# CNC_IO_Buffer_Cape.net
KiCad netlist of a schematic drawn in EAGLE
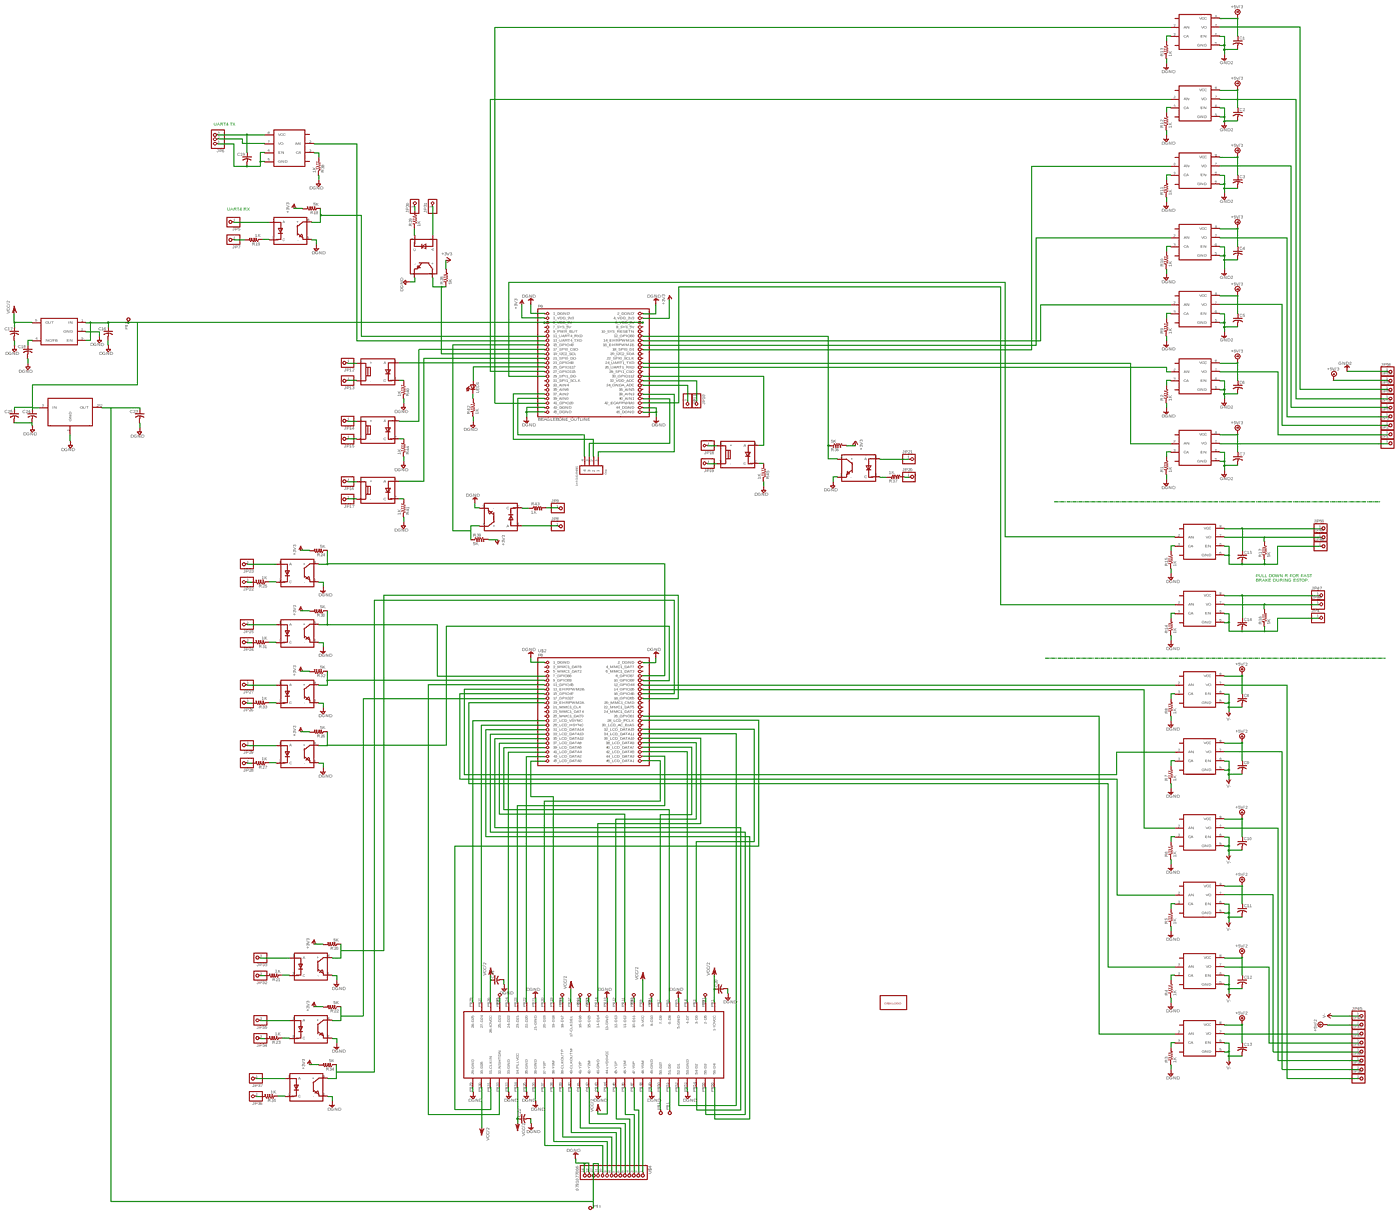
[diagram p0: schematic, sheet 1, overview]
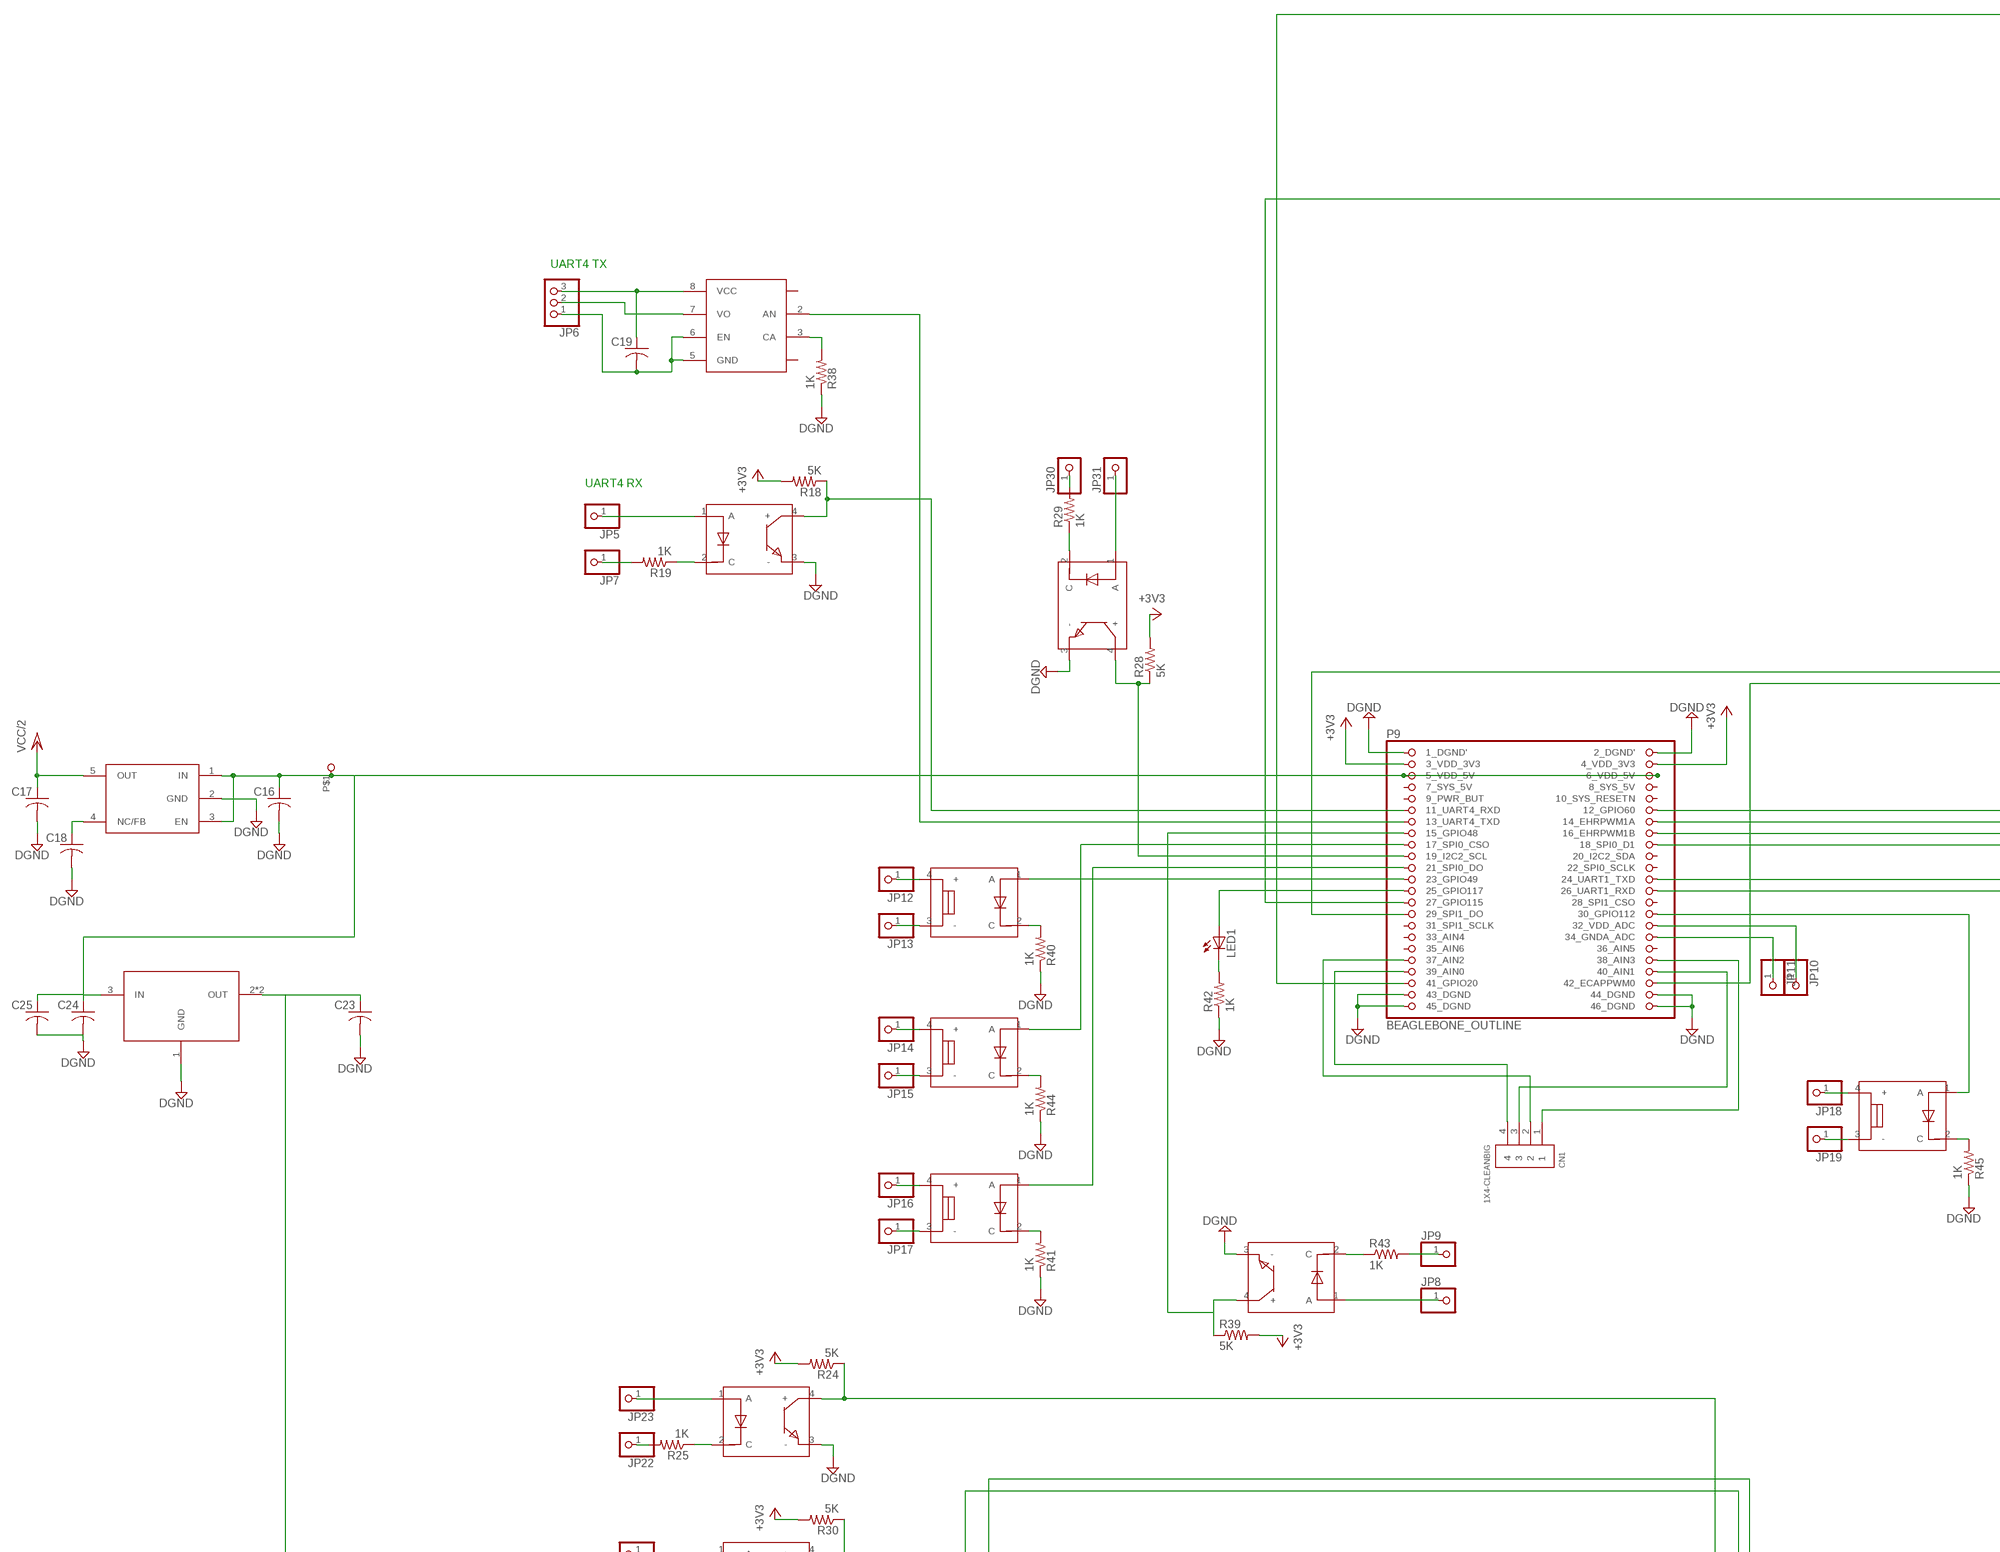
[diagram p1: schematic, sheet 1, part 1 of 4]
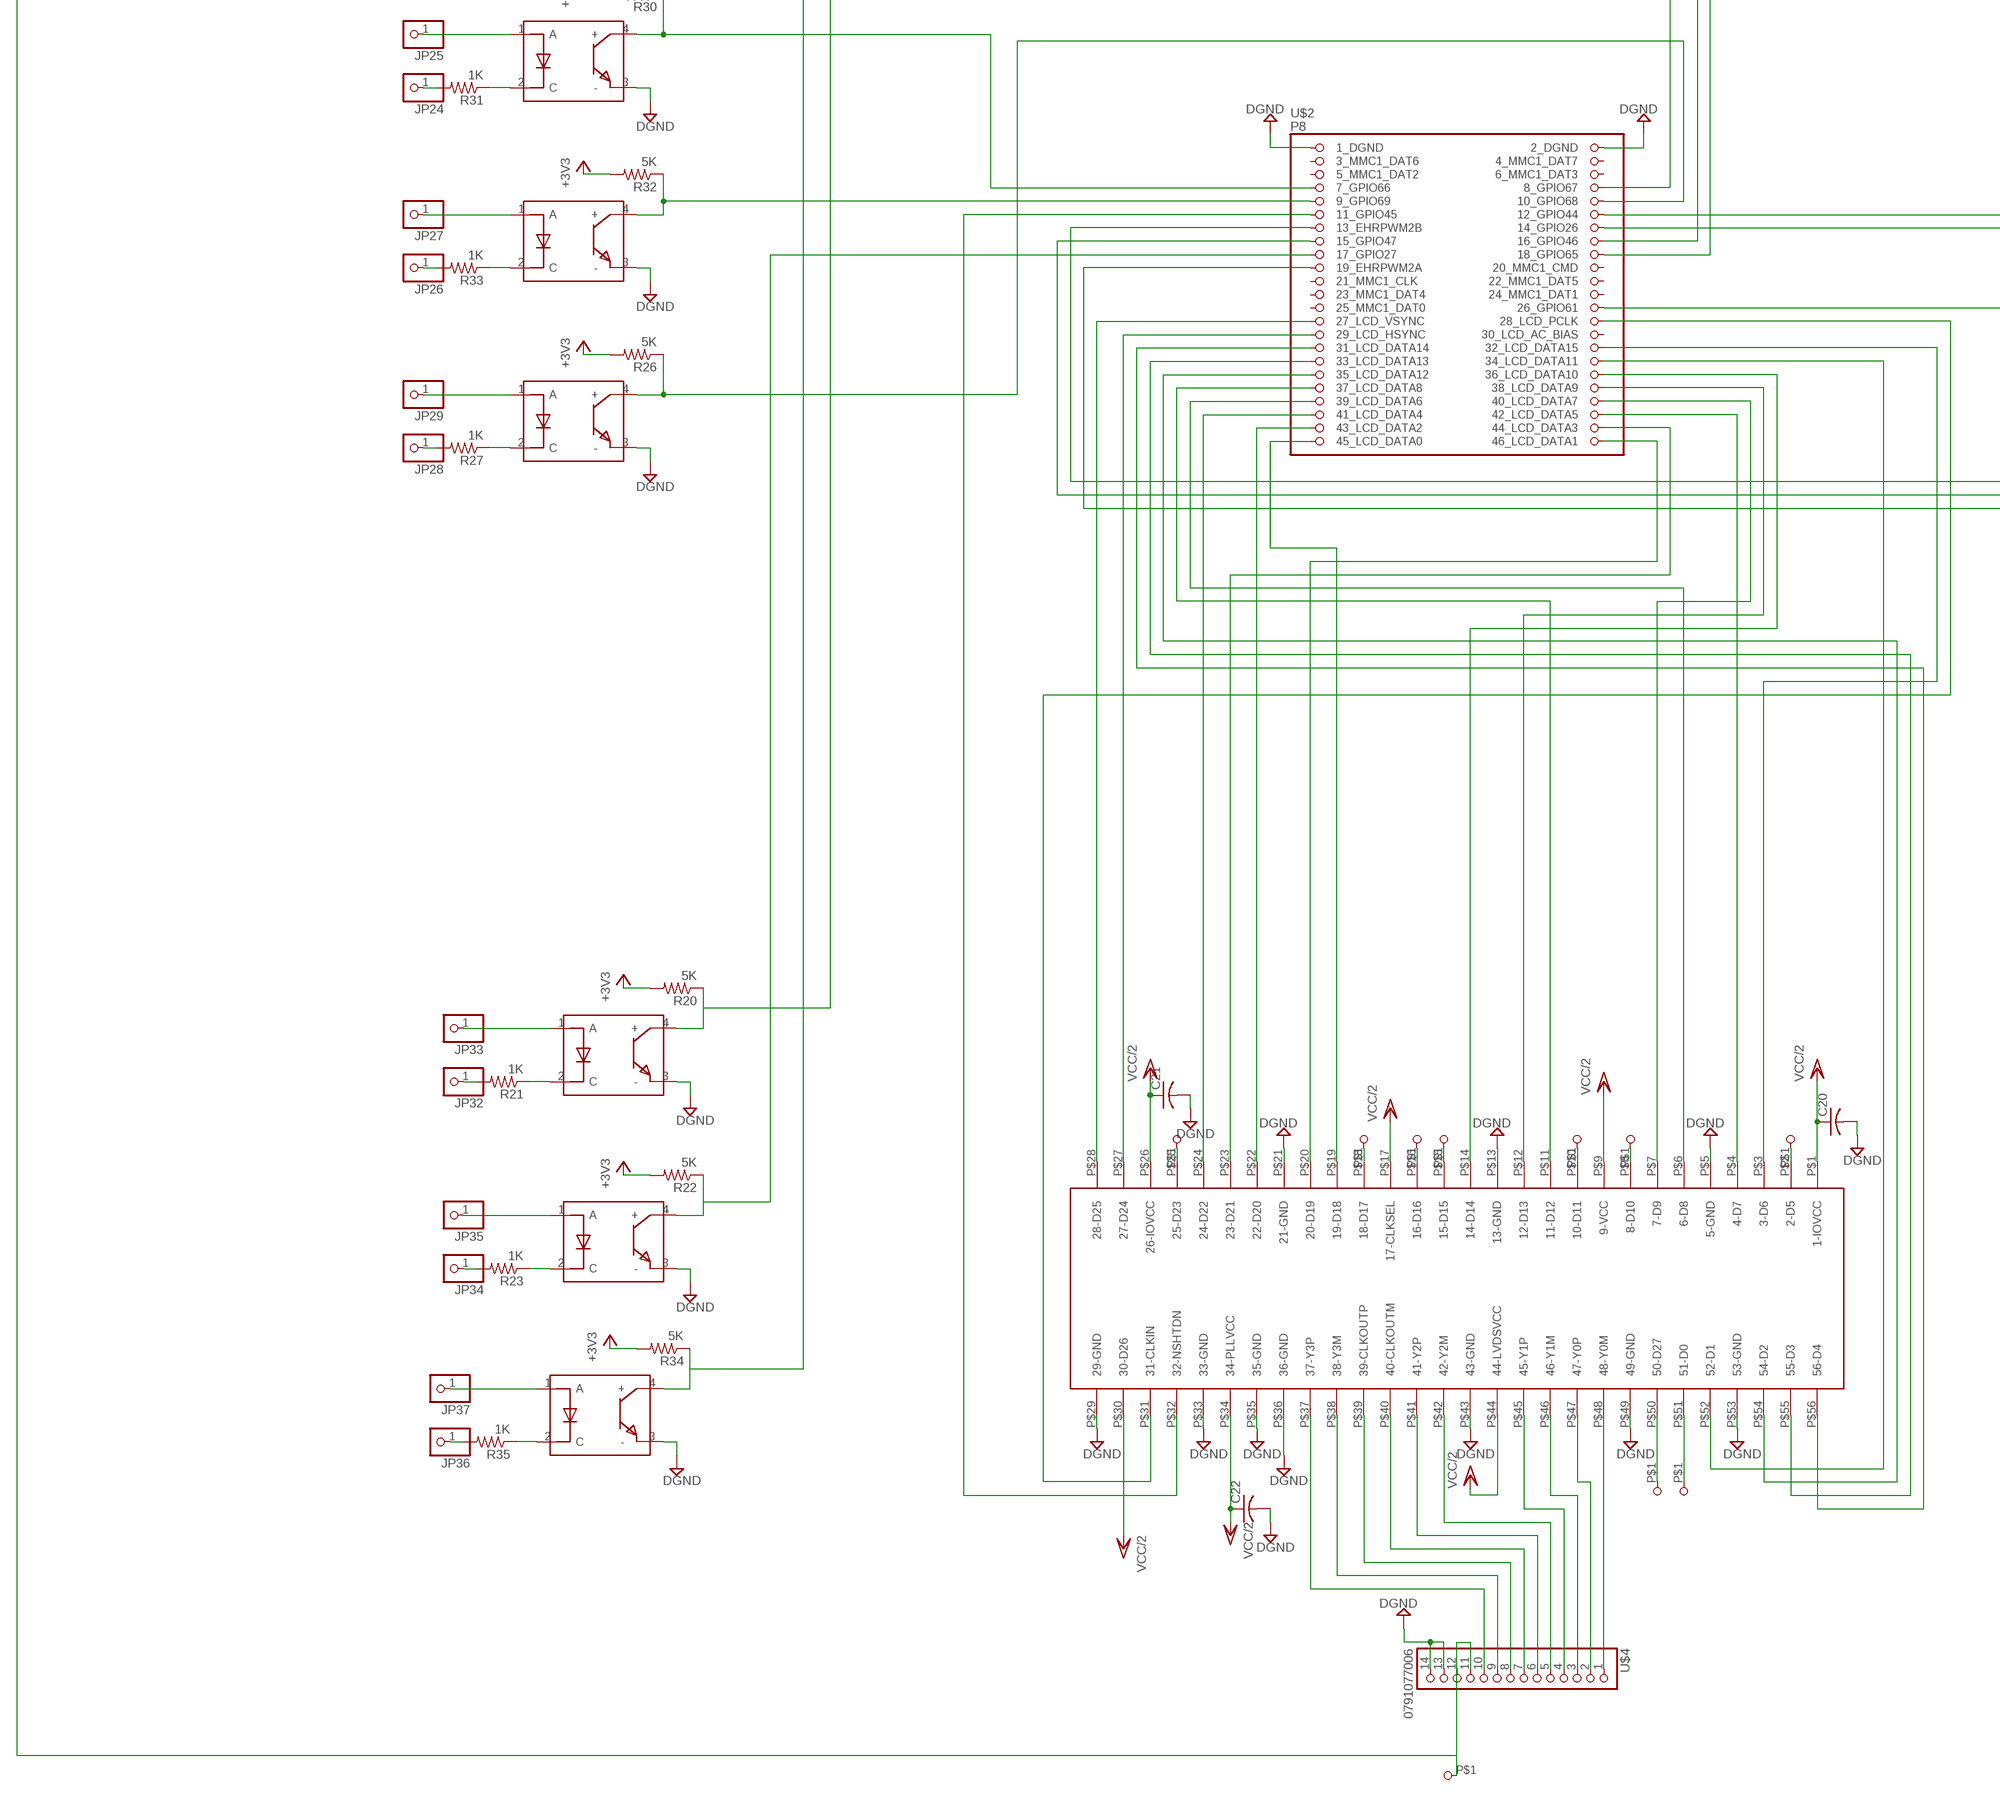
[diagram p2: schematic, sheet 1, part 2 of 4]
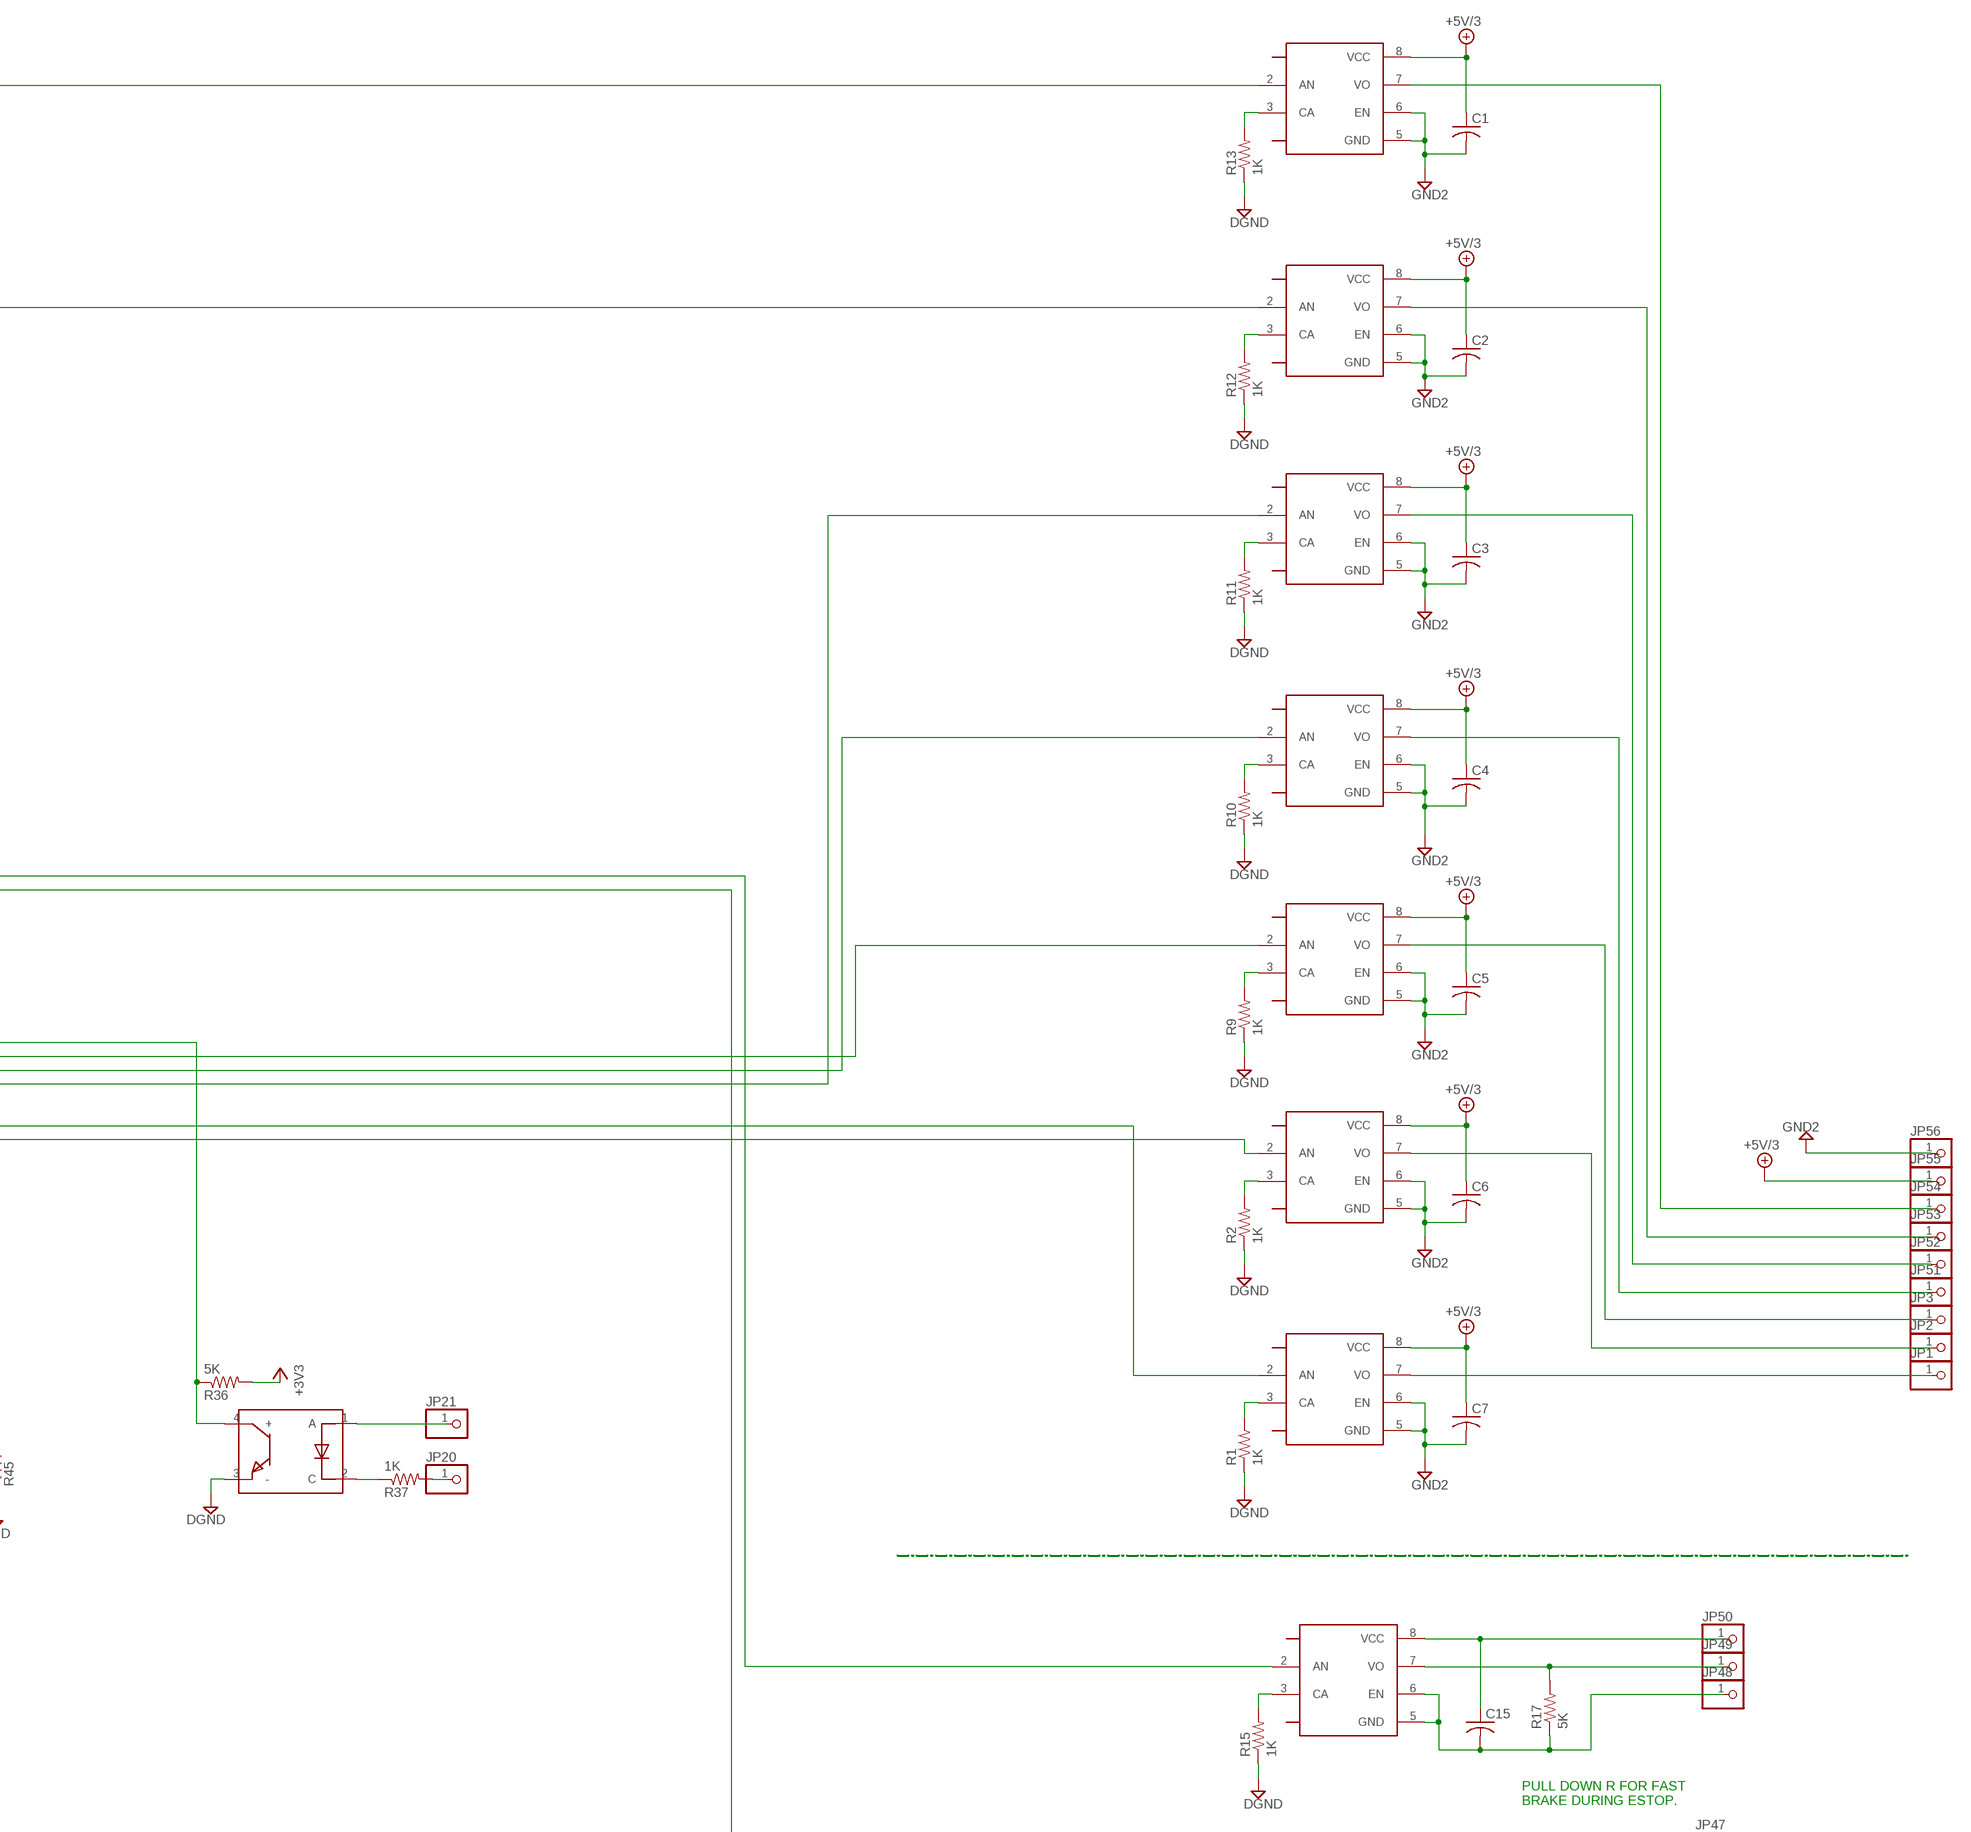
[diagram p3: schematic, sheet 1, part 3 of 4]
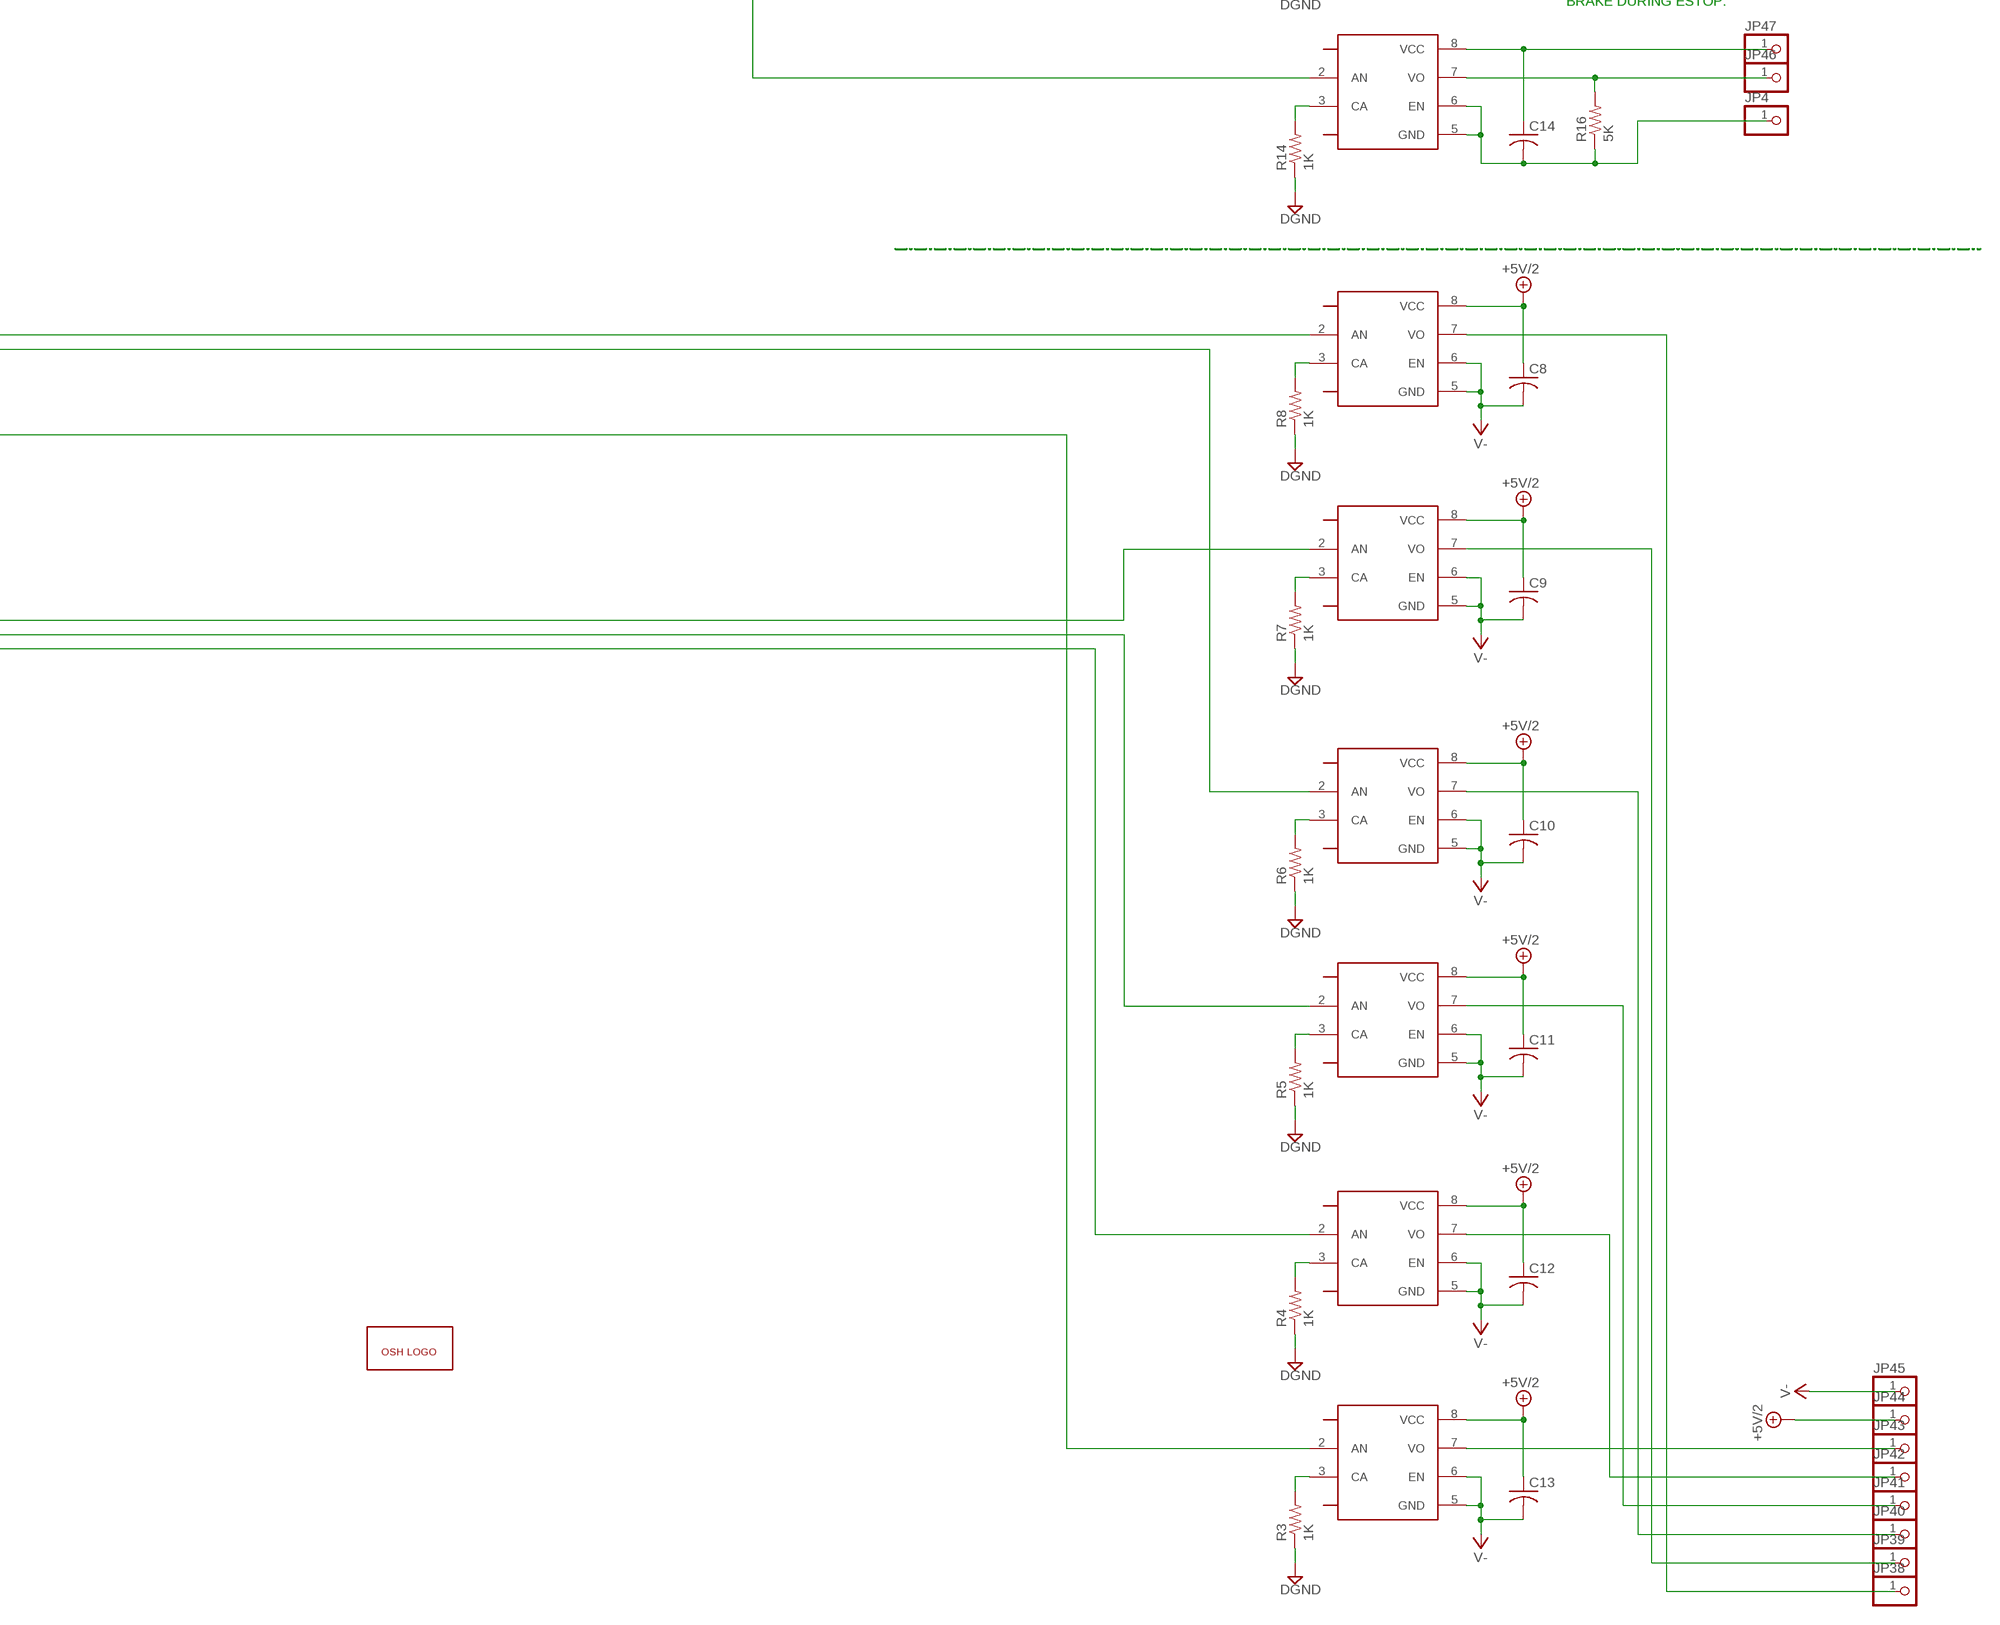
[diagram p4: schematic, sheet 1, part 4 of 4]

(export (version "E")
  (design (tool "Eeschema 10.0.6"))
  (components
    (comp (ref "0000")
      (value "TLP2200F")
      (footprint "eagle-import:DIL08-ROUND")
      (libsource (lib "eagle-import") (part "TLP2200F"))
    )
    (comp (ref "8.12")
      (value "TLP2200F")
      (footprint "eagle-import:DIL08-ROUND")
      (libsource (lib "eagle-import") (part "TLP2200F"))
    )
    (comp (ref "8.13")
      (value "TLP2200F")
      (footprint "eagle-import:DIL08-ROUND")
      (libsource (lib "eagle-import") (part "TLP2200F"))
    )
    (comp (ref "8.14")
      (value "TLP2200F")
      (footprint "eagle-import:DIL08-ROUND")
      (libsource (lib "eagle-import") (part "TLP2200F"))
    )
    (comp (ref "8.15")
      (value "TLP2200F")
      (footprint "eagle-import:DIL08-ROUND")
      (libsource (lib "eagle-import") (part "TLP2200F"))
    )
    (comp (ref "8.19")
      (value "TLP2200F")
      (footprint "eagle-import:DIL08-ROUND")
      (libsource (lib "eagle-import") (part "TLP2200F"))
    )
    (comp (ref "8.26")
      (value "TLP2200F")
      (footprint "eagle-import:DIL08-ROUND")
      (libsource (lib "eagle-import") (part "TLP2200F"))
    )
    (comp (ref "9.3")
      (value "TLP2200F")
      (footprint "eagle-import:DIL08-ROUND")
      (libsource (lib "eagle-import") (part "TLP2200F"))
    )
    (comp (ref "9.14")
      (value "TLP2200F")
      (footprint "eagle-import:DIL08-ROUND")
      (libsource (lib "eagle-import") (part "TLP2200F"))
    )
    (comp (ref "9.16")
      (value "TLP2200F")
      (footprint "eagle-import:DIL08-ROUND")
      (libsource (lib "eagle-import") (part "TLP2200F"))
    )
    (comp (ref "9.18")
      (value "TLP2200F")
      (footprint "eagle-import:DIL08-ROUND")
      (libsource (lib "eagle-import") (part "TLP2200F"))
    )
    (comp (ref "9.24")
      (value "TLP2200F")
      (footprint "eagle-import:DIL08-ROUND")
      (libsource (lib "eagle-import") (part "TLP2200F"))
    )
    (comp (ref "9.26")
      (value "TLP2200F")
      (footprint "eagle-import:DIL08-ROUND")
      (libsource (lib "eagle-import") (part "TLP2200F"))
    )
    (comp (ref "9.27")
      (value "TLP2200F")
      (footprint "eagle-import:DIL08-ROUND")
      (libsource (lib "eagle-import") (part "TLP2200F"))
    )
    (comp (ref "9.41")
      (value "TLP2200F")
      (footprint "eagle-import:DIL08-ROUND")
      (libsource (lib "eagle-import") (part "TLP2200F"))
    )
    (comp (ref "1111")
      (value "TLP2200F")
      (footprint "eagle-import:DIL08-ROUND")
      (libsource (lib "eagle-import") (part "TLP2200F"))
    )
    (comp (ref "C1")
      (value "C-USC0805K")
      (footprint "eagle-import:C0805K")
      (libsource (lib "eagle-import") (part "rcl_C-USC0805K"))
    )
    (comp (ref "C2")
      (value "C-USC0805K")
      (footprint "eagle-import:C0805K")
      (libsource (lib "eagle-import") (part "rcl_C-USC0805K"))
    )
    (comp (ref "C3")
      (value "C-USC0805K")
      (footprint "eagle-import:C0805K")
      (libsource (lib "eagle-import") (part "rcl_C-USC0805K"))
    )
    (comp (ref "C4")
      (value "C-USC0805K")
      (footprint "eagle-import:C0805K")
      (libsource (lib "eagle-import") (part "rcl_C-USC0805K"))
    )
    (comp (ref "C5")
      (value "C-USC0805K")
      (footprint "eagle-import:C0805K")
      (libsource (lib "eagle-import") (part "rcl_C-USC0805K"))
    )
    (comp (ref "C6")
      (value "C-USC0805K")
      (footprint "eagle-import:C0805K")
      (libsource (lib "eagle-import") (part "rcl_C-USC0805K"))
    )
    (comp (ref "C7")
      (value "C-USC0805K")
      (footprint "eagle-import:C0805K")
      (libsource (lib "eagle-import") (part "rcl_C-USC0805K"))
    )
    (comp (ref "C8")
      (value "C-USC0805K")
      (footprint "eagle-import:C0805K")
      (libsource (lib "eagle-import") (part "rcl_C-USC0805K"))
    )
    (comp (ref "C9")
      (value "C-USC0805K")
      (footprint "eagle-import:C0805K")
      (libsource (lib "eagle-import") (part "rcl_C-USC0805K"))
    )
    (comp (ref "C10")
      (value "C-USC0805K")
      (footprint "eagle-import:C0805K")
      (libsource (lib "eagle-import") (part "rcl_C-USC0805K"))
    )
    (comp (ref "C11")
      (value "C-USC0805K")
      (footprint "eagle-import:C0805K")
      (libsource (lib "eagle-import") (part "rcl_C-USC0805K"))
    )
    (comp (ref "C12")
      (value "C-USC0805K")
      (footprint "eagle-import:C0805K")
      (libsource (lib "eagle-import") (part "rcl_C-USC0805K"))
    )
    (comp (ref "C13")
      (value "C-USC0805K")
      (footprint "eagle-import:C0805K")
      (libsource (lib "eagle-import") (part "rcl_C-USC0805K"))
    )
    (comp (ref "C14")
      (value "C-USC0805K")
      (footprint "eagle-import:C0805K")
      (libsource (lib "eagle-import") (part "rcl_C-USC0805K"))
    )
    (comp (ref "C15")
      (value "C-USC0805K")
      (footprint "eagle-import:C0805K")
      (libsource (lib "eagle-import") (part "rcl_C-USC0805K"))
    )
    (comp (ref "C16")
      (value "C-USC0805K")
      (footprint "eagle-import:C0805K")
      (libsource (lib "eagle-import") (part "C-USC0805K"))
    )
    (comp (ref "C17")
      (value "C-USC0805K")
      (footprint "eagle-import:C0805K")
      (libsource (lib "eagle-import") (part "C-USC0805K"))
    )
    (comp (ref "C18")
      (value "C-USC0402")
      (footprint "eagle-import:C0402")
      (libsource (lib "eagle-import") (part "C-USC0402"))
    )
    (comp (ref "C19")
      (value "C-USC0805K")
      (footprint "eagle-import:C0805K")
      (libsource (lib "eagle-import") (part "rcl_C-USC0805K"))
    )
    (comp (ref "C20")
      (value "C-USC0402")
      (footprint "eagle-import:C0402")
      (libsource (lib "eagle-import") (part "C-USC0402"))
    )
    (comp (ref "C21")
      (value "C-USC0402")
      (footprint "eagle-import:C0402")
      (libsource (lib "eagle-import") (part "C-USC0402"))
    )
    (comp (ref "C22")
      (value "C-USC0402")
      (footprint "eagle-import:C0402")
      (libsource (lib "eagle-import") (part "C-USC0402"))
    )
    (comp (ref "C23")
      (value "C-USC0805K")
      (footprint "eagle-import:C0805K")
      (libsource (lib "eagle-import") (part "C-USC0805K"))
    )
    (comp (ref "C24")
      (value "C-USC0805K")
      (footprint "eagle-import:C0805K")
      (libsource (lib "eagle-import") (part "C-USC0805K"))
    )
    (comp (ref "C25")
      (value "C-USC0402")
      (footprint "eagle-import:C0402")
      (libsource (lib "eagle-import") (part "C-USC0402"))
    )
    (comp (ref "CN1")
      (value "1X4-CLEANBIG")
      (footprint "eagle-import:1X04-CLEANBIG")
      (libsource (lib "eagle-import") (part "1X4-CLEANBIG"))
    )
    (comp (ref "JP1")
      (value "PINHD-1X1CB")
      (footprint "eagle-import:1X01-CLEANBIG")
      (libsource (lib "eagle-import") (part "PINHD-1X1CB"))
    )
    (comp (ref "JP2")
      (value "PINHD-1X1CB")
      (footprint "eagle-import:1X01-CLEANBIG")
      (libsource (lib "eagle-import") (part "PINHD-1X1CB"))
    )
    (comp (ref "JP3")
      (value "PINHD-1X1CB")
      (footprint "eagle-import:1X01-CLEANBIG")
      (libsource (lib "eagle-import") (part "PINHD-1X1CB"))
    )
    (comp (ref "JP4")
      (value "PINHD-1X1CB")
      (footprint "eagle-import:1X01-CLEANBIG")
      (libsource (lib "eagle-import") (part "PINHD-1X1CB"))
    )
    (comp (ref "JP5")
      (value "PINHD-1X1CB")
      (footprint "eagle-import:1X01-CLEANBIG")
      (libsource (lib "eagle-import") (part "PINHD-1X1CB"))
    )
    (comp (ref "JP6")
      (value "PINHD-1X3CB")
      (footprint "eagle-import:1X03-CLEANBIG")
      (libsource (lib "eagle-import") (part "PINHD-1X3CB"))
    )
    (comp (ref "JP7")
      (value "PINHD-1X1CB")
      (footprint "eagle-import:1X01-CLEANBIG")
      (libsource (lib "eagle-import") (part "PINHD-1X1CB"))
    )
    (comp (ref "JP8")
      (value "PINHD-1X1CB")
      (footprint "eagle-import:1X01-CLEANBIG")
      (libsource (lib "eagle-import") (part "PINHD-1X1CB"))
    )
    (comp (ref "JP9")
      (value "PINHD-1X1CB")
      (footprint "eagle-import:1X01-CLEANBIG")
      (libsource (lib "eagle-import") (part "PINHD-1X1CB"))
    )
    (comp (ref "JP10")
      (value "PINHD-1X1CB")
      (footprint "eagle-import:1X01-CLEANBIG")
      (libsource (lib "eagle-import") (part "PINHD-1X1CB"))
    )
    (comp (ref "JP11")
      (value "PINHD-1X1CB")
      (footprint "eagle-import:1X01-CLEANBIG")
      (libsource (lib "eagle-import") (part "PINHD-1X1CB"))
    )
    (comp (ref "JP12")
      (value "PINHD-1X1CB")
      (footprint "eagle-import:1X01-CLEANBIG")
      (libsource (lib "eagle-import") (part "PINHD-1X1CB"))
    )
    (comp (ref "JP13")
      (value "PINHD-1X1CB")
      (footprint "eagle-import:1X01-CLEANBIG")
      (libsource (lib "eagle-import") (part "PINHD-1X1CB"))
    )
    (comp (ref "JP14")
      (value "PINHD-1X1CB")
      (footprint "eagle-import:1X01-CLEANBIG")
      (libsource (lib "eagle-import") (part "PINHD-1X1CB"))
    )
    (comp (ref "JP15")
      (value "PINHD-1X1CB")
      (footprint "eagle-import:1X01-CLEANBIG")
      (libsource (lib "eagle-import") (part "PINHD-1X1CB"))
    )
    (comp (ref "JP16")
      (value "PINHD-1X1CB")
      (footprint "eagle-import:1X01-CLEANBIG")
      (libsource (lib "eagle-import") (part "PINHD-1X1CB"))
    )
    (comp (ref "JP17")
      (value "PINHD-1X1CB")
      (footprint "eagle-import:1X01-CLEANBIG")
      (libsource (lib "eagle-import") (part "PINHD-1X1CB"))
    )
    (comp (ref "JP18")
      (value "PINHD-1X1CB")
      (footprint "eagle-import:1X01-CLEANBIG")
      (libsource (lib "eagle-import") (part "PINHD-1X1CB"))
    )
    (comp (ref "JP19")
      (value "PINHD-1X1CB")
      (footprint "eagle-import:1X01-CLEANBIG")
      (libsource (lib "eagle-import") (part "PINHD-1X1CB"))
    )
    (comp (ref "JP20")
      (value "PINHD-1X1CB")
      (footprint "eagle-import:1X01-CLEANBIG")
      (libsource (lib "eagle-import") (part "PINHD-1X1CB"))
    )
    (comp (ref "JP21")
      (value "PINHD-1X1CB")
      (footprint "eagle-import:1X01-CLEANBIG")
      (libsource (lib "eagle-import") (part "PINHD-1X1CB"))
    )
    (comp (ref "JP22")
      (value "PINHD-1X1CB")
      (footprint "eagle-import:1X01-CLEANBIG")
      (libsource (lib "eagle-import") (part "PINHD-1X1CB"))
    )
    (comp (ref "JP23")
      (value "PINHD-1X1CB")
      (footprint "eagle-import:1X01-CLEANBIG")
      (libsource (lib "eagle-import") (part "PINHD-1X1CB"))
    )
    (comp (ref "JP24")
      (value "PINHD-1X1CB")
      (footprint "eagle-import:1X01-CLEANBIG")
      (libsource (lib "eagle-import") (part "PINHD-1X1CB"))
    )
    (comp (ref "JP25")
      (value "PINHD-1X1CB")
      (footprint "eagle-import:1X01-CLEANBIG")
      (libsource (lib "eagle-import") (part "PINHD-1X1CB"))
    )
    (comp (ref "JP26")
      (value "PINHD-1X1CB")
      (footprint "eagle-import:1X01-CLEANBIG")
      (libsource (lib "eagle-import") (part "PINHD-1X1CB"))
    )
    (comp (ref "JP27")
      (value "PINHD-1X1CB")
      (footprint "eagle-import:1X01-CLEANBIG")
      (libsource (lib "eagle-import") (part "PINHD-1X1CB"))
    )
    (comp (ref "JP28")
      (value "PINHD-1X1CB")
      (footprint "eagle-import:1X01-CLEANBIG")
      (libsource (lib "eagle-import") (part "PINHD-1X1CB"))
    )
    (comp (ref "JP29")
      (value "PINHD-1X1CB")
      (footprint "eagle-import:1X01-CLEANBIG")
      (libsource (lib "eagle-import") (part "PINHD-1X1CB"))
    )
    (comp (ref "JP30")
      (value "PINHD-1X1CB")
      (footprint "eagle-import:1X01-CLEANBIG")
      (libsource (lib "eagle-import") (part "PINHD-1X1CB"))
    )
    (comp (ref "JP31")
      (value "PINHD-1X1CB")
      (footprint "eagle-import:1X01-CLEANBIG")
      (libsource (lib "eagle-import") (part "PINHD-1X1CB"))
    )
    (comp (ref "JP32")
      (value "PINHD-1X1CB")
      (footprint "eagle-import:1X01-CLEANBIG")
      (libsource (lib "eagle-import") (part "PINHD-1X1CB"))
    )
    (comp (ref "JP33")
      (value "PINHD-1X1CB")
      (footprint "eagle-import:1X01-CLEANBIG")
      (libsource (lib "eagle-import") (part "PINHD-1X1CB"))
    )
    (comp (ref "JP34")
      (value "PINHD-1X1CB")
      (footprint "eagle-import:1X01-CLEANBIG")
      (libsource (lib "eagle-import") (part "PINHD-1X1CB"))
    )
    (comp (ref "JP35")
      (value "PINHD-1X1CB")
      (footprint "eagle-import:1X01-CLEANBIG")
      (libsource (lib "eagle-import") (part "PINHD-1X1CB"))
    )
    (comp (ref "JP36")
      (value "PINHD-1X1CB")
      (footprint "eagle-import:1X01-CLEANBIG")
      (libsource (lib "eagle-import") (part "PINHD-1X1CB"))
    )
    (comp (ref "JP37")
      (value "PINHD-1X1CB")
      (footprint "eagle-import:1X01-CLEANBIG")
      (libsource (lib "eagle-import") (part "PINHD-1X1CB"))
    )
    (comp (ref "JP38")
      (value "PINHD-1X1CB")
      (footprint "eagle-import:1X01-CLEANBIG")
      (libsource (lib "eagle-import") (part "PINHD-1X1CB"))
    )
    (comp (ref "JP39")
      (value "PINHD-1X1CB")
      (footprint "eagle-import:1X01-CLEANBIG")
      (libsource (lib "eagle-import") (part "PINHD-1X1CB"))
    )
    (comp (ref "JP40")
      (value "PINHD-1X1CB")
      (footprint "eagle-import:1X01-CLEANBIG")
      (libsource (lib "eagle-import") (part "PINHD-1X1CB"))
    )
    (comp (ref "JP41")
      (value "PINHD-1X1CB")
      (footprint "eagle-import:1X01-CLEANBIG")
      (libsource (lib "eagle-import") (part "PINHD-1X1CB"))
    )
    (comp (ref "JP42")
      (value "PINHD-1X1CB")
      (footprint "eagle-import:1X01-CLEANBIG")
      (libsource (lib "eagle-import") (part "PINHD-1X1CB"))
    )
    (comp (ref "JP43")
      (value "PINHD-1X1CB")
      (footprint "eagle-import:1X01-CLEANBIG")
      (libsource (lib "eagle-import") (part "PINHD-1X1CB"))
    )
    (comp (ref "JP44")
      (value "PINHD-1X1CB")
      (footprint "eagle-import:1X01-CLEANBIG")
      (libsource (lib "eagle-import") (part "PINHD-1X1CB"))
    )
    (comp (ref "JP45")
      (value "PINHD-1X1CB")
      (footprint "eagle-import:1X01-CLEANBIG")
      (libsource (lib "eagle-import") (part "PINHD-1X1CB"))
    )
    (comp (ref "JP46")
      (value "PINHD-1X1CB")
      (footprint "eagle-import:1X01-CLEANBIG")
      (libsource (lib "eagle-import") (part "PINHD-1X1CB"))
    )
    (comp (ref "JP47")
      (value "PINHD-1X1CB")
      (footprint "eagle-import:1X01-CLEANBIG")
      (libsource (lib "eagle-import") (part "PINHD-1X1CB"))
    )
    (comp (ref "JP48")
      (value "PINHD-1X1CB")
      (footprint "eagle-import:1X01-CLEANBIG")
      (libsource (lib "eagle-import") (part "PINHD-1X1CB"))
    )
    (comp (ref "JP49")
      (value "PINHD-1X1CB")
      (footprint "eagle-import:1X01-CLEANBIG")
      (libsource (lib "eagle-import") (part "PINHD-1X1CB"))
    )
    (comp (ref "JP50")
      (value "PINHD-1X1CB")
      (footprint "eagle-import:1X01-CLEANBIG")
      (libsource (lib "eagle-import") (part "PINHD-1X1CB"))
    )
    (comp (ref "JP51")
      (value "PINHD-1X1CB")
      (footprint "eagle-import:1X01-CLEANBIG")
      (libsource (lib "eagle-import") (part "PINHD-1X1CB"))
    )
    (comp (ref "JP52")
      (value "PINHD-1X1CB")
      (footprint "eagle-import:1X01-CLEANBIG")
      (libsource (lib "eagle-import") (part "PINHD-1X1CB"))
    )
    (comp (ref "JP53")
      (value "PINHD-1X1CB")
      (footprint "eagle-import:1X01-CLEANBIG")
      (libsource (lib "eagle-import") (part "PINHD-1X1CB"))
    )
    (comp (ref "JP54")
      (value "PINHD-1X1CB")
      (footprint "eagle-import:1X01-CLEANBIG")
      (libsource (lib "eagle-import") (part "PINHD-1X1CB"))
    )
    (comp (ref "JP55")
      (value "PINHD-1X1CB")
      (footprint "eagle-import:1X01-CLEANBIG")
      (libsource (lib "eagle-import") (part "PINHD-1X1CB"))
    )
    (comp (ref "JP56")
      (value "PINHD-1X1CB")
      (footprint "eagle-import:1X01-CLEANBIG")
      (libsource (lib "eagle-import") (part "PINHD-1X1CB"))
    )
    (comp (ref "LED1")
      (value "LED5MM")
      (footprint "eagle-import:LED5MM")
      (libsource (lib "eagle-import") (part "LED5MM"))
    )
    (comp (ref "R1")
      (value "1K")
      (footprint "eagle-import:R0603")
      (libsource (lib "eagle-import") (part "R-US_R0603"))
    )
    (comp (ref "R2")
      (value "1K")
      (footprint "eagle-import:R0603")
      (libsource (lib "eagle-import") (part "R-US_R0603"))
    )
    (comp (ref "R3")
      (value "1K")
      (footprint "eagle-import:R0603")
      (libsource (lib "eagle-import") (part "R-US_R0603"))
    )
    (comp (ref "R4")
      (value "1K")
      (footprint "eagle-import:R0603")
      (libsource (lib "eagle-import") (part "R-US_R0603"))
    )
    (comp (ref "R5")
      (value "1K")
      (footprint "eagle-import:R0603")
      (libsource (lib "eagle-import") (part "R-US_R0603"))
    )
    (comp (ref "R6")
      (value "1K")
      (footprint "eagle-import:R0603")
      (libsource (lib "eagle-import") (part "R-US_R0603"))
    )
    (comp (ref "R7")
      (value "1K")
      (footprint "eagle-import:R0603")
      (libsource (lib "eagle-import") (part "R-US_R0603"))
    )
    (comp (ref "R8")
      (value "1K")
      (footprint "eagle-import:R0603")
      (libsource (lib "eagle-import") (part "R-US_R0603"))
    )
    (comp (ref "R9")
      (value "1K")
      (footprint "eagle-import:R0603")
      (libsource (lib "eagle-import") (part "R-US_R0603"))
    )
    (comp (ref "R10")
      (value "1K")
      (footprint "eagle-import:R0603")
      (libsource (lib "eagle-import") (part "R-US_R0603"))
    )
    (comp (ref "R11")
      (value "1K")
      (footprint "eagle-import:R0603")
      (libsource (lib "eagle-import") (part "R-US_R0603"))
    )
    (comp (ref "R12")
      (value "1K")
      (footprint "eagle-import:R0603")
      (libsource (lib "eagle-import") (part "R-US_R0603"))
    )
    (comp (ref "R13")
      (value "1K")
      (footprint "eagle-import:R0603")
      (libsource (lib "eagle-import") (part "R-US_R0603"))
    )
    (comp (ref "R14")
      (value "1K")
      (footprint "eagle-import:R0603")
      (libsource (lib "eagle-import") (part "R-US_R0603"))
    )
    (comp (ref "R15")
      (value "1K")
      (footprint "eagle-import:R0603")
      (libsource (lib "eagle-import") (part "R-US_R0603"))
    )
    (comp (ref "R16")
      (value "5K")
      (footprint "eagle-import:R0603")
      (libsource (lib "eagle-import") (part "R-US_R0603"))
    )
    (comp (ref "R17")
      (value "5K")
      (footprint "eagle-import:R0603")
      (libsource (lib "eagle-import") (part "R-US_R0603"))
    )
    (comp (ref "R18")
      (value "5K")
      (footprint "eagle-import:R0603")
      (libsource (lib "eagle-import") (part "R-US_R0603"))
    )
    (comp (ref "R19")
      (value "1K")
      (footprint "eagle-import:R0603")
      (libsource (lib "eagle-import") (part "R-US_R0603"))
    )
    (comp (ref "R20")
      (value "5K")
      (footprint "eagle-import:R0603")
      (libsource (lib "eagle-import") (part "R-US_R0603"))
    )
    (comp (ref "R21")
      (value "1K")
      (footprint "eagle-import:R0603")
      (libsource (lib "eagle-import") (part "R-US_R0603"))
    )
    (comp (ref "R22")
      (value "5K")
      (footprint "eagle-import:R0603")
      (libsource (lib "eagle-import") (part "R-US_R0603"))
    )
    (comp (ref "R23")
      (value "1K")
      (footprint "eagle-import:R0603")
      (libsource (lib "eagle-import") (part "R-US_R0603"))
    )
    (comp (ref "R24")
      (value "5K")
      (footprint "eagle-import:R0603")
      (libsource (lib "eagle-import") (part "R-US_R0603"))
    )
    (comp (ref "R25")
      (value "1K")
      (footprint "eagle-import:R0603")
      (libsource (lib "eagle-import") (part "R-US_R0603"))
    )
    (comp (ref "R26")
      (value "5K")
      (footprint "eagle-import:R0603")
      (libsource (lib "eagle-import") (part "R-US_R0603"))
    )
    (comp (ref "R27")
      (value "1K")
      (footprint "eagle-import:R0603")
      (libsource (lib "eagle-import") (part "R-US_R0603"))
    )
    (comp (ref "R28")
      (value "5K")
      (footprint "eagle-import:R0603")
      (libsource (lib "eagle-import") (part "R-US_R0603"))
    )
    (comp (ref "R29")
      (value "1K")
      (footprint "eagle-import:R0603")
      (libsource (lib "eagle-import") (part "R-US_R0603"))
    )
    (comp (ref "R30")
      (value "5K")
      (footprint "eagle-import:R0603")
      (libsource (lib "eagle-import") (part "R-US_R0603"))
    )
    (comp (ref "R31")
      (value "1K")
      (footprint "eagle-import:R0603")
      (libsource (lib "eagle-import") (part "R-US_R0603"))
    )
    (comp (ref "R32")
      (value "5K")
      (footprint "eagle-import:R0603")
      (libsource (lib "eagle-import") (part "R-US_R0603"))
    )
    (comp (ref "R33")
      (value "1K")
      (footprint "eagle-import:R0603")
      (libsource (lib "eagle-import") (part "R-US_R0603"))
    )
    (comp (ref "R34")
      (value "5K")
      (footprint "eagle-import:R0603")
      (libsource (lib "eagle-import") (part "R-US_R0603"))
    )
    (comp (ref "R35")
      (value "1K")
      (footprint "eagle-import:R0603")
      (libsource (lib "eagle-import") (part "R-US_R0603"))
    )
    (comp (ref "R36")
      (value "5K")
      (footprint "eagle-import:R0603")
      (libsource (lib "eagle-import") (part "R-US_R0603"))
    )
    (comp (ref "R37")
      (value "1K")
      (footprint "eagle-import:R0603")
      (libsource (lib "eagle-import") (part "R-US_R0603"))
    )
    (comp (ref "R38")
      (value "1K")
      (footprint "eagle-import:R0603")
      (libsource (lib "eagle-import") (part "R-US_R0603"))
    )
    (comp (ref "R39")
      (value "5K")
      (footprint "eagle-import:R0603")
      (libsource (lib "eagle-import") (part "R-US_R0603"))
    )
    (comp (ref "R40")
      (value "1K")
      (footprint "eagle-import:R0603")
      (libsource (lib "eagle-import") (part "R-US_R0603"))
    )
    (comp (ref "R41")
      (value "1K")
      (footprint "eagle-import:R0603")
      (libsource (lib "eagle-import") (part "R-US_R0603"))
    )
    (comp (ref "R42")
      (value "1K")
      (footprint "eagle-import:R0603")
      (libsource (lib "eagle-import") (part "R-US_R0603"))
    )
    (comp (ref "R43")
      (value "1K")
      (footprint "eagle-import:R0603")
      (libsource (lib "eagle-import") (part "R-US_R0603"))
    )
    (comp (ref "R44")
      (value "1K")
      (footprint "eagle-import:R0603")
      (libsource (lib "eagle-import") (part "R-US_R0603"))
    )
    (comp (ref "R45")
      (value "1K")
      (footprint "eagle-import:R0603")
      (libsource (lib "eagle-import") (part "R-US_R0603"))
    )
    (comp (ref "SPICS1")
      (value "TLP222A")
      (footprint "eagle-import:DIL04-ROUND")
      (libsource (lib "eagle-import") (part "TLP222A"))
    )
    (comp (ref "SPICS2")
      (value "TLP222A")
      (footprint "eagle-import:DIL04-ROUND")
      (libsource (lib "eagle-import") (part "TLP222A"))
    )
    (comp (ref "SPICS3")
      (value "TLP222A")
      (footprint "eagle-import:DIL04-ROUND")
      (libsource (lib "eagle-import") (part "TLP222A"))
    )
    (comp (ref "SPICS4")
      (value "TLP222A")
      (footprint "eagle-import:DIL04-ROUND")
      (libsource (lib "eagle-import") (part "TLP222A"))
    )
    (comp (ref "TPS73133")
      (value "TPS76350DBVR")
      (footprint "eagle-import:SOT23-5L")
      (libsource (lib "eagle-import") (part "TPS76350DBVR"))
    )
    (comp (ref "U$1")
      (value "FOD817B")
      (footprint "eagle-import:DIL04-ROUND")
      (libsource (lib "eagle-import") (part "FOD817B"))
    )
    (comp (ref "U$2")
      (value "BEAGLEBONE_OUTLINE")
      (footprint "eagle-import:BEAGLEBONE_SHIELD")
      (libsource (lib "eagle-import") (part "BEAGLEBONE_OUTLINE"))
    )
    (comp (ref "U$3")
      (value "SN75LVDS83B")
      (footprint "eagle-import:DGG0056A")
      (libsource (lib "eagle-import") (part "SN75LVDS83B"))
    )
    (comp (ref "U$4")
      (value "0791077006")
      (footprint "eagle-import:0791077006")
      (libsource (lib "eagle-import") (part "0791077006"))
    )
    (comp (ref "U$5")
      (value "DEAN_SMALL_VIA")
      (footprint "eagle-import:DEAN_SMALL_VIA")
      (libsource (lib "eagle-import") (part "DEAN_SMALL_VIA"))
    )
    (comp (ref "U$6")
      (value "FOD817B")
      (footprint "eagle-import:DIL04-ROUND")
      (libsource (lib "eagle-import") (part "FOD817B"))
    )
    (comp (ref "U$7")
      (value "FOD817B")
      (footprint "eagle-import:DIL04-ROUND")
      (libsource (lib "eagle-import") (part "FOD817B"))
    )
    (comp (ref "U$8")
      (value "FOD817B")
      (footprint "eagle-import:DIL04-ROUND")
      (libsource (lib "eagle-import") (part "FOD817B"))
    )
    (comp (ref "U$9")
      (value "FOD817B")
      (footprint "eagle-import:DIL04-ROUND")
      (libsource (lib "eagle-import") (part "FOD817B"))
    )
    (comp (ref "U$10")
      (value "FOD817B")
      (footprint "eagle-import:DIL04-ROUND")
      (libsource (lib "eagle-import") (part "FOD817B"))
    )
    (comp (ref "U$11")
      (value "FOD817B")
      (footprint "eagle-import:DIL04-ROUND")
      (libsource (lib "eagle-import") (part "FOD817B"))
    )
    (comp (ref "U$12")
      (value "FOD817B")
      (footprint "eagle-import:DIL04-ROUND")
      (libsource (lib "eagle-import") (part "FOD817B"))
    )
    (comp (ref "U$13")
      (value "FOD817B")
      (footprint "eagle-import:DIL04-ROUND")
      (libsource (lib "eagle-import") (part "FOD817B"))
    )
    (comp (ref "U$14")
      (value "FOD817B")
      (footprint "eagle-import:DIL04-ROUND")
      (libsource (lib "eagle-import") (part "FOD817B"))
    )
    (comp (ref "U$15")
      (value "FOD817B")
      (footprint "eagle-import:DIL04-ROUND")
      (libsource (lib "eagle-import") (part "FOD817B"))
    )
    (comp (ref "U$16")
      (value "DEAN_SMALL_VIA")
      (footprint "eagle-import:DEAN_SMALL_VIA")
      (libsource (lib "eagle-import") (part "DEAN_SMALL_VIA"))
    )
    (comp (ref "U$17")
      (value "OSH_LOGO")
      (footprint "eagle-import:OSH_LOGO")
      (libsource (lib "eagle-import") (part "OSH_LOGO"))
    )
    (comp (ref "U$18")
      (value "LM1117")
      (footprint "eagle-import:SOT223")
      (libsource (lib "eagle-import") (part "LM1117"))
    )
    (comp (ref "U$19")
      (value "DEAN_SMALL_VIA")
      (footprint "eagle-import:DEAN_SMALL_VIA")
      (libsource (lib "eagle-import") (part "DEAN_SMALL_VIA"))
    )
    (comp (ref "U$20")
      (value "DEAN_SMALL_VIA")
      (footprint "eagle-import:DEAN_SMALL_VIA")
      (libsource (lib "eagle-import") (part "DEAN_SMALL_VIA"))
    )
    (comp (ref "U$21")
      (value "DEAN_SMALL_VIA")
      (footprint "eagle-import:DEAN_SMALL_VIA")
      (libsource (lib "eagle-import") (part "DEAN_SMALL_VIA"))
    )
    (comp (ref "U$22")
      (value "DEAN_SMALL_VIA")
      (footprint "eagle-import:DEAN_SMALL_VIA")
      (libsource (lib "eagle-import") (part "DEAN_SMALL_VIA"))
    )
    (comp (ref "U$23")
      (value "DEAN_SMALL_VIA")
      (footprint "eagle-import:DEAN_SMALL_VIA")
      (libsource (lib "eagle-import") (part "DEAN_SMALL_VIA"))
    )
    (comp (ref "U$24")
      (value "DEAN_SMALL_VIA")
      (footprint "eagle-import:DEAN_SMALL_VIA")
      (libsource (lib "eagle-import") (part "DEAN_SMALL_VIA"))
    )
    (comp (ref "U$25")
      (value "DEAN_SMALL_VIA")
      (footprint "eagle-import:DEAN_SMALL_VIA")
      (libsource (lib "eagle-import") (part "DEAN_SMALL_VIA"))
    )
    (comp (ref "U$32")
      (value "DEAN_SMALL_VIA")
      (footprint "eagle-import:DEAN_SMALL_VIA")
      (libsource (lib "eagle-import") (part "DEAN_SMALL_VIA"))
    )
    (comp (ref "U$33")
      (value "DEAN_SMALL_VIA")
      (footprint "eagle-import:DEAN_SMALL_VIA")
      (libsource (lib "eagle-import") (part "DEAN_SMALL_VIA"))
    )
  )
  (nets
    (net (code "1") (name "+3V3") (class "Default")
      (node (ref "R18") (pin "2") (pinfunction "2_2") (pintype "passive"))
      (node (ref "R20") (pin "2") (pinfunction "2_2") (pintype "passive"))
      (node (ref "R22") (pin "2") (pinfunction "2_2") (pintype "passive"))
      (node (ref "R24") (pin "2") (pinfunction "2_2") (pintype "passive"))
      (node (ref "R26") (pin "2") (pinfunction "2_2") (pintype "passive"))
      (node (ref "R28") (pin "2") (pinfunction "2_2") (pintype "passive"))
      (node (ref "R30") (pin "2") (pinfunction "2_2") (pintype "passive"))
      (node (ref "R32") (pin "2") (pinfunction "2_2") (pintype "passive"))
      (node (ref "R34") (pin "2") (pinfunction "2_2") (pintype "passive"))
      (node (ref "R36") (pin "2") (pinfunction "2_2") (pintype "passive"))
      (node (ref "R39") (pin "2") (pinfunction "2_2") (pintype "passive"))
      (node (ref "U$2") (pin "49") (pinfunction "3_VDD_3V3_49") (pintype "power_in"))
      (node (ref "U$2") (pin "50") (pinfunction "4_VDD_3V3_50") (pintype "power_in"))
    )
    (net (code "2") (name "+5V{slash}2") (class "Default")
      (node (ref "8.12") (pin "8") (pinfunction "VCC_8") (pintype "bidirectional"))
      (node (ref "8.13") (pin "8") (pinfunction "VCC_8") (pintype "bidirectional"))
      (node (ref "8.14") (pin "8") (pinfunction "VCC_8") (pintype "bidirectional"))
      (node (ref "8.15") (pin "8") (pinfunction "VCC_8") (pintype "bidirectional"))
      (node (ref "8.19") (pin "8") (pinfunction "VCC_8") (pintype "bidirectional"))
      (node (ref "8.26") (pin "8") (pinfunction "VCC_8") (pintype "bidirectional"))
      (node (ref "C10") (pin "1") (pinfunction "1_1") (pintype "passive"))
      (node (ref "C11") (pin "1") (pinfunction "1_1") (pintype "passive"))
      (node (ref "C12") (pin "1") (pinfunction "1_1") (pintype "passive"))
      (node (ref "C13") (pin "1") (pinfunction "1_1") (pintype "passive"))
      (node (ref "C8") (pin "1") (pinfunction "1_1") (pintype "passive"))
      (node (ref "C9") (pin "1") (pinfunction "1_1") (pintype "passive"))
      (node (ref "JP44") (pin "1") (pinfunction "1_1") (pintype "passive"))
    )
    (net (code "3") (name "+5V{slash}3") (class "Default")
      (node (ref "9.14") (pin "8") (pinfunction "VCC_8") (pintype "bidirectional"))
      (node (ref "9.16") (pin "8") (pinfunction "VCC_8") (pintype "bidirectional"))
      (node (ref "9.18") (pin "8") (pinfunction "VCC_8") (pintype "bidirectional"))
      (node (ref "9.24") (pin "8") (pinfunction "VCC_8") (pintype "bidirectional"))
      (node (ref "9.26") (pin "8") (pinfunction "VCC_8") (pintype "bidirectional"))
      (node (ref "9.27") (pin "8") (pinfunction "VCC_8") (pintype "bidirectional"))
      (node (ref "9.41") (pin "8") (pinfunction "VCC_8") (pintype "bidirectional"))
      (node (ref "C1") (pin "1") (pinfunction "1_1") (pintype "passive"))
      (node (ref "C2") (pin "1") (pinfunction "1_1") (pintype "passive"))
      (node (ref "C3") (pin "1") (pinfunction "1_1") (pintype "passive"))
      (node (ref "C4") (pin "1") (pinfunction "1_1") (pintype "passive"))
      (node (ref "C5") (pin "1") (pinfunction "1_1") (pintype "passive"))
      (node (ref "C6") (pin "1") (pinfunction "1_1") (pintype "passive"))
      (node (ref "C7") (pin "1") (pinfunction "1_1") (pintype "passive"))
      (node (ref "JP55") (pin "1") (pinfunction "1_1") (pintype "passive"))
    )
    (net (code "4") (name "/7_SYS_5V") (class "Default")
      (node (ref "U$2") (pin "53") (pinfunction "7_SYS_5V_53") (pintype "power_in"))
    )
    (net (code "5") (name "DGND") (class "Default")
      (node (ref "C16") (pin "2") (pinfunction "2_2") (pintype "passive"))
      (node (ref "C17") (pin "2") (pinfunction "2_2") (pintype "passive"))
      (node (ref "C18") (pin "2") (pinfunction "2_2") (pintype "passive"))
      (node (ref "C20") (pin "2") (pinfunction "2_2") (pintype "passive"))
      (node (ref "C21") (pin "2") (pinfunction "2_2") (pintype "passive"))
      (node (ref "C22") (pin "2") (pinfunction "2_2") (pintype "passive"))
      (node (ref "C23") (pin "2") (pinfunction "2_2") (pintype "passive"))
      (node (ref "C24") (pin "2") (pinfunction "2_2") (pintype "passive"))
      (node (ref "C25") (pin "2") (pinfunction "2_2") (pintype "passive"))
      (node (ref "R1") (pin "1") (pinfunction "1_1") (pintype "passive"))
      (node (ref "R10") (pin "1") (pinfunction "1_1") (pintype "passive"))
      (node (ref "R11") (pin "1") (pinfunction "1_1") (pintype "passive"))
      (node (ref "R12") (pin "1") (pinfunction "1_1") (pintype "passive"))
      (node (ref "R13") (pin "1") (pinfunction "1_1") (pintype "passive"))
      (node (ref "R14") (pin "1") (pinfunction "1_1") (pintype "passive"))
      (node (ref "R15") (pin "1") (pinfunction "1_1") (pintype "passive"))
      (node (ref "R2") (pin "1") (pinfunction "1_1") (pintype "passive"))
      (node (ref "R3") (pin "1") (pinfunction "1_1") (pintype "passive"))
      (node (ref "R38") (pin "1") (pinfunction "1_1") (pintype "passive"))
      (node (ref "R4") (pin "1") (pinfunction "1_1") (pintype "passive"))
      (node (ref "R40") (pin "1") (pinfunction "1_1") (pintype "passive"))
      (node (ref "R41") (pin "1") (pinfunction "1_1") (pintype "passive"))
      (node (ref "R42") (pin "1") (pinfunction "1_1") (pintype "passive"))
      (node (ref "R44") (pin "1") (pinfunction "1_1") (pintype "passive"))
      (node (ref "R45") (pin "1") (pinfunction "1_1") (pintype "passive"))
      (node (ref "R5") (pin "1") (pinfunction "1_1") (pintype "passive"))
      (node (ref "R6") (pin "1") (pinfunction "1_1") (pintype "passive"))
      (node (ref "R7") (pin "1") (pinfunction "1_1") (pintype "passive"))
      (node (ref "R8") (pin "1") (pinfunction "1_1") (pintype "passive"))
      (node (ref "R9") (pin "1") (pinfunction "1_1") (pintype "passive"))
      (node (ref "TPS73133") (pin "2") (pinfunction "GND_2") (pintype "bidirectional"))
      (node (ref "U$1") (pin "3") (pinfunction "-_3") (pintype "bidirectional"))
      (node (ref "U$10") (pin "3") (pinfunction "-_3") (pintype "bidirectional"))
      (node (ref "U$11") (pin "3") (pinfunction "-_3") (pintype "bidirectional"))
      (node (ref "U$12") (pin "3") (pinfunction "-_3") (pintype "bidirectional"))
      (node (ref "U$13") (pin "3") (pinfunction "-_3") (pintype "bidirectional"))
      (node (ref "U$14") (pin "3") (pinfunction "-_3") (pintype "bidirectional"))
      (node (ref "U$15") (pin "3") (pinfunction "-_3") (pintype "bidirectional"))
      (node (ref "U$18") (pin "1") (pinfunction "GND_1") (pintype "bidirectional"))
      (node (ref "U$2") (pin "1") (pinfunction "1_DGND_1") (pintype "power_in"))
      (node (ref "U$2") (pin "2") (pinfunction "2_DGND_2") (pintype "power_in"))
      (node (ref "U$2") (pin "47") (pinfunction "1_DGND'_47") (pintype "power_in"))
      (node (ref "U$2") (pin "48") (pinfunction "2_DGND'_48") (pintype "power_in"))
      (node (ref "U$2") (pin "89") (pinfunction "43_DGND_89") (pintype "power_in"))
      (node (ref "U$2") (pin "90") (pinfunction "44_DGND_90") (pintype "power_in"))
      (node (ref "U$2") (pin "91") (pinfunction "45_DGND_91") (pintype "power_in"))
      (node (ref "U$2") (pin "92") (pinfunction "46_DGND_92") (pintype "power_in"))
      (node (ref "U$3") (pin "P$13") (pinfunction "13-GND_P$13") (pintype "bidirectional"))
      (node (ref "U$3") (pin "P$21") (pinfunction "21-GND_P$21") (pintype "bidirectional"))
      (node (ref "U$3") (pin "P$29") (pinfunction "29-GND_P$29") (pintype "bidirectional"))
      (node (ref "U$3") (pin "P$33") (pinfunction "33-GND_P$33") (pintype "bidirectional"))
      (node (ref "U$3") (pin "P$35") (pinfunction "35-GND_P$35") (pintype "bidirectional"))
      (node (ref "U$3") (pin "P$36") (pinfunction "36-GND_P$36") (pintype "bidirectional"))
      (node (ref "U$3") (pin "P$43") (pinfunction "43-GND_P$43") (pintype "bidirectional"))
      (node (ref "U$3") (pin "P$49") (pinfunction "49-GND_P$49") (pintype "bidirectional"))
      (node (ref "U$3") (pin "P$5") (pinfunction "5-GND_P$5") (pintype "bidirectional"))
      (node (ref "U$3") (pin "P$53") (pinfunction "53-GND_P$53") (pintype "bidirectional"))
      (node (ref "U$4") (pin "13") (pinfunction "13_13") (pintype "passive"))
      (node (ref "U$4") (pin "14") (pinfunction "14_14") (pintype "passive"))
      (node (ref "U$6") (pin "3") (pinfunction "-_3") (pintype "bidirectional"))
      (node (ref "U$7") (pin "3") (pinfunction "-_3") (pintype "bidirectional"))
      (node (ref "U$8") (pin "3") (pinfunction "-_3") (pintype "bidirectional"))
      (node (ref "U$9") (pin "3") (pinfunction "-_3") (pintype "bidirectional"))
    )
    (net (code "6") (name "GND2") (class "Default")
      (node (ref "9.14") (pin "5") (pinfunction "GND_5") (pintype "bidirectional"))
      (node (ref "9.14") (pin "6") (pinfunction "EN_6") (pintype "bidirectional"))
      (node (ref "9.16") (pin "5") (pinfunction "GND_5") (pintype "bidirectional"))
      (node (ref "9.16") (pin "6") (pinfunction "EN_6") (pintype "bidirectional"))
      (node (ref "9.18") (pin "5") (pinfunction "GND_5") (pintype "bidirectional"))
      (node (ref "9.18") (pin "6") (pinfunction "EN_6") (pintype "bidirectional"))
      (node (ref "9.24") (pin "5") (pinfunction "GND_5") (pintype "bidirectional"))
      (node (ref "9.24") (pin "6") (pinfunction "EN_6") (pintype "bidirectional"))
      (node (ref "9.26") (pin "5") (pinfunction "GND_5") (pintype "bidirectional"))
      (node (ref "9.26") (pin "6") (pinfunction "EN_6") (pintype "bidirectional"))
      (node (ref "9.27") (pin "5") (pinfunction "GND_5") (pintype "bidirectional"))
      (node (ref "9.27") (pin "6") (pinfunction "EN_6") (pintype "bidirectional"))
      (node (ref "9.41") (pin "5") (pinfunction "GND_5") (pintype "bidirectional"))
      (node (ref "9.41") (pin "6") (pinfunction "EN_6") (pintype "bidirectional"))
      (node (ref "C1") (pin "2") (pinfunction "2_2") (pintype "passive"))
      (node (ref "C2") (pin "2") (pinfunction "2_2") (pintype "passive"))
      (node (ref "C3") (pin "2") (pinfunction "2_2") (pintype "passive"))
      (node (ref "C4") (pin "2") (pinfunction "2_2") (pintype "passive"))
      (node (ref "C5") (pin "2") (pinfunction "2_2") (pintype "passive"))
      (node (ref "C6") (pin "2") (pinfunction "2_2") (pintype "passive"))
      (node (ref "C7") (pin "2") (pinfunction "2_2") (pintype "passive"))
      (node (ref "JP56") (pin "1") (pinfunction "1_1") (pintype "passive"))
    )
    (net (code "7") (name "Net-(0000-AN)") (class "Default")
      (node (ref "0000") (pin "2") (pinfunction "AN_2") (pintype "bidirectional"))
      (node (ref "U$2") (pin "88") (pinfunction "42_ECAPPWM0_88") (pintype "passive"))
    )
    (net (code "8") (name "Net-(0000-CA)") (class "Default")
      (node (ref "0000") (pin "3") (pinfunction "CA_3") (pintype "bidirectional"))
      (node (ref "R14") (pin "2") (pinfunction "2_2") (pintype "passive"))
    )
    (net (code "9") (name "Net-(0000-EN)") (class "Default")
      (node (ref "0000") (pin "5") (pinfunction "GND_5") (pintype "bidirectional"))
      (node (ref "0000") (pin "6") (pinfunction "EN_6") (pintype "bidirectional"))
      (node (ref "C14") (pin "2") (pinfunction "2_2") (pintype "passive"))
      (node (ref "JP4") (pin "1") (pinfunction "1_1") (pintype "passive"))
      (node (ref "R16") (pin "1") (pinfunction "1_1") (pintype "passive"))
    )
    (net (code "10") (name "Net-(0000-VCC)") (class "Default")
      (node (ref "0000") (pin "8") (pinfunction "VCC_8") (pintype "bidirectional"))
      (node (ref "C14") (pin "1") (pinfunction "1_1") (pintype "passive"))
      (node (ref "JP47") (pin "1") (pinfunction "1_1") (pintype "passive"))
    )
    (net (code "11") (name "Net-(0000-VO)") (class "Default")
      (node (ref "0000") (pin "7") (pinfunction "VO_7") (pintype "bidirectional"))
      (node (ref "JP46") (pin "1") (pinfunction "1_1") (pintype "passive"))
      (node (ref "R16") (pin "2") (pinfunction "2_2") (pintype "passive"))
    )
    (net (code "12") (name "Net-(8.12-AN)") (class "Default")
      (node (ref "8.12") (pin "2") (pinfunction "AN_2") (pintype "bidirectional"))
      (node (ref "U$2") (pin "12") (pinfunction "12_GPIO44_12") (pintype "passive"))
    )
    (net (code "13") (name "Net-(8.12-CA)") (class "Default")
      (node (ref "8.12") (pin "3") (pinfunction "CA_3") (pintype "bidirectional"))
      (node (ref "R8") (pin "2") (pinfunction "2_2") (pintype "passive"))
    )
    (net (code "14") (name "Net-(8.12-VO)") (class "Default")
      (node (ref "8.12") (pin "7") (pinfunction "VO_7") (pintype "bidirectional"))
      (node (ref "JP38") (pin "1") (pinfunction "1_1") (pintype "passive"))
    )
    (net (code "15") (name "Net-(8.13-AN)") (class "Default")
      (node (ref "8.13") (pin "2") (pinfunction "AN_2") (pintype "bidirectional"))
      (node (ref "U$2") (pin "13") (pinfunction "13_EHRPWM2B_13") (pintype "passive"))
    )
    (net (code "16") (name "Net-(8.13-CA)") (class "Default")
      (node (ref "8.13") (pin "3") (pinfunction "CA_3") (pintype "bidirectional"))
      (node (ref "R7") (pin "2") (pinfunction "2_2") (pintype "passive"))
    )
    (net (code "17") (name "Net-(8.13-VO)") (class "Default")
      (node (ref "8.13") (pin "7") (pinfunction "VO_7") (pintype "bidirectional"))
      (node (ref "JP39") (pin "1") (pinfunction "1_1") (pintype "passive"))
    )
    (net (code "18") (name "Net-(8.14-AN)") (class "Default")
      (node (ref "8.14") (pin "2") (pinfunction "AN_2") (pintype "bidirectional"))
      (node (ref "U$2") (pin "14") (pinfunction "14_GPIO26_14") (pintype "passive"))
    )
    (net (code "19") (name "Net-(8.14-CA)") (class "Default")
      (node (ref "8.14") (pin "3") (pinfunction "CA_3") (pintype "bidirectional"))
      (node (ref "R6") (pin "2") (pinfunction "2_2") (pintype "passive"))
    )
    (net (code "20") (name "Net-(8.14-VO)") (class "Default")
      (node (ref "8.14") (pin "7") (pinfunction "VO_7") (pintype "bidirectional"))
      (node (ref "JP40") (pin "1") (pinfunction "1_1") (pintype "passive"))
    )
    (net (code "21") (name "Net-(8.15-AN)") (class "Default")
      (node (ref "8.15") (pin "2") (pinfunction "AN_2") (pintype "bidirectional"))
      (node (ref "U$2") (pin "15") (pinfunction "15_GPIO47_15") (pintype "passive"))
    )
    (net (code "22") (name "Net-(8.15-CA)") (class "Default")
      (node (ref "8.15") (pin "3") (pinfunction "CA_3") (pintype "bidirectional"))
      (node (ref "R5") (pin "2") (pinfunction "2_2") (pintype "passive"))
    )
    (net (code "23") (name "Net-(8.15-VO)") (class "Default")
      (node (ref "8.15") (pin "7") (pinfunction "VO_7") (pintype "bidirectional"))
      (node (ref "JP41") (pin "1") (pinfunction "1_1") (pintype "passive"))
    )
    (net (code "24") (name "Net-(8.19-AN)") (class "Default")
      (node (ref "8.19") (pin "2") (pinfunction "AN_2") (pintype "bidirectional"))
      (node (ref "U$2") (pin "19") (pinfunction "19_EHRPWM2A_19") (pintype "passive"))
    )
    (net (code "25") (name "Net-(8.19-CA)") (class "Default")
      (node (ref "8.19") (pin "3") (pinfunction "CA_3") (pintype "bidirectional"))
      (node (ref "R4") (pin "2") (pinfunction "2_2") (pintype "passive"))
    )
    (net (code "26") (name "Net-(8.19-VO)") (class "Default")
      (node (ref "8.19") (pin "7") (pinfunction "VO_7") (pintype "bidirectional"))
      (node (ref "JP42") (pin "1") (pinfunction "1_1") (pintype "passive"))
    )
    (net (code "27") (name "Net-(8.26-AN)") (class "Default")
      (node (ref "8.26") (pin "2") (pinfunction "AN_2") (pintype "bidirectional"))
      (node (ref "U$2") (pin "26") (pinfunction "26_GPIO61_26") (pintype "passive"))
    )
    (net (code "28") (name "Net-(8.26-CA)") (class "Default")
      (node (ref "8.26") (pin "3") (pinfunction "CA_3") (pintype "bidirectional"))
      (node (ref "R3") (pin "2") (pinfunction "2_2") (pintype "passive"))
    )
    (net (code "29") (name "Net-(8.26-VO)") (class "Default")
      (node (ref "8.26") (pin "7") (pinfunction "VO_7") (pintype "bidirectional"))
      (node (ref "JP43") (pin "1") (pinfunction "1_1") (pintype "passive"))
    )
    (net (code "30") (name "Net-(9.3-AN)") (class "Default")
      (node (ref "9.3") (pin "2") (pinfunction "AN_2") (pintype "bidirectional"))
      (node (ref "U$2") (pin "59") (pinfunction "13_UART4_TXD_59") (pintype "passive"))
    )
    (net (code "31") (name "Net-(9.3-CA)") (class "Default")
      (node (ref "9.3") (pin "3") (pinfunction "CA_3") (pintype "bidirectional"))
      (node (ref "R38") (pin "2") (pinfunction "2_2") (pintype "passive"))
    )
    (net (code "32") (name "Net-(9.3-EN)") (class "Default")
      (node (ref "9.3") (pin "5") (pinfunction "GND_5") (pintype "bidirectional"))
      (node (ref "9.3") (pin "6") (pinfunction "EN_6") (pintype "bidirectional"))
      (node (ref "C19") (pin "2") (pinfunction "2_2") (pintype "passive"))
      (node (ref "JP6") (pin "1") (pinfunction "1_1") (pintype "passive"))
    )
    (net (code "33") (name "Net-(9.3-VCC)") (class "Default")
      (node (ref "9.3") (pin "8") (pinfunction "VCC_8") (pintype "bidirectional"))
      (node (ref "C19") (pin "1") (pinfunction "1_1") (pintype "passive"))
      (node (ref "JP6") (pin "3") (pinfunction "3_3") (pintype "passive"))
    )
    (net (code "34") (name "Net-(9.3-VO)") (class "Default")
      (node (ref "9.3") (pin "7") (pinfunction "VO_7") (pintype "bidirectional"))
      (node (ref "JP6") (pin "2") (pinfunction "2_2") (pintype "passive"))
    )
    (net (code "35") (name "Net-(9.14-AN)") (class "Default")
      (node (ref "9.14") (pin "2") (pinfunction "AN_2") (pintype "bidirectional"))
      (node (ref "U$2") (pin "60") (pinfunction "14_EHRPWM1A_60") (pintype "passive"))
    )
    (net (code "36") (name "Net-(9.14-CA)") (class "Default")
      (node (ref "9.14") (pin "3") (pinfunction "CA_3") (pintype "bidirectional"))
      (node (ref "R9") (pin "2") (pinfunction "2_2") (pintype "passive"))
    )
    (net (code "37") (name "Net-(9.14-VO)") (class "Default")
      (node (ref "9.14") (pin "7") (pinfunction "VO_7") (pintype "bidirectional"))
      (node (ref "JP3") (pin "1") (pinfunction "1_1") (pintype "passive"))
    )
    (net (code "38") (name "Net-(9.16-AN)") (class "Default")
      (node (ref "9.16") (pin "2") (pinfunction "AN_2") (pintype "bidirectional"))
      (node (ref "U$2") (pin "62") (pinfunction "16_EHRPWM1B_62") (pintype "passive"))
    )
    (net (code "39") (name "Net-(9.16-CA)") (class "Default")
      (node (ref "9.16") (pin "3") (pinfunction "CA_3") (pintype "bidirectional"))
      (node (ref "R10") (pin "2") (pinfunction "2_2") (pintype "passive"))
    )
    (net (code "40") (name "Net-(9.16-VO)") (class "Default")
      (node (ref "9.16") (pin "7") (pinfunction "VO_7") (pintype "bidirectional"))
      (node (ref "JP51") (pin "1") (pinfunction "1_1") (pintype "passive"))
    )
    (net (code "41") (name "Net-(9.18-AN)") (class "Default")
      (node (ref "9.18") (pin "2") (pinfunction "AN_2") (pintype "bidirectional"))
      (node (ref "U$2") (pin "64") (pinfunction "18_SPI0_D1_64") (pintype "passive"))
    )
    (net (code "42") (name "Net-(9.18-CA)") (class "Default")
      (node (ref "9.18") (pin "3") (pinfunction "CA_3") (pintype "bidirectional"))
      (node (ref "R11") (pin "2") (pinfunction "2_2") (pintype "passive"))
    )
    (net (code "43") (name "Net-(9.18-VO)") (class "Default")
      (node (ref "9.18") (pin "7") (pinfunction "VO_7") (pintype "bidirectional"))
      (node (ref "JP52") (pin "1") (pinfunction "1_1") (pintype "passive"))
    )
    (net (code "44") (name "Net-(9.24-AN)") (class "Default")
      (node (ref "9.24") (pin "2") (pinfunction "AN_2") (pintype "bidirectional"))
      (node (ref "U$2") (pin "70") (pinfunction "24_UART1_TXD_70") (pintype "passive"))
    )
    (net (code "45") (name "Net-(9.24-CA)") (class "Default")
      (node (ref "9.24") (pin "3") (pinfunction "CA_3") (pintype "bidirectional"))
      (node (ref "R1") (pin "2") (pinfunction "2_2") (pintype "passive"))
    )
    (net (code "46") (name "Net-(9.24-VO)") (class "Default")
      (node (ref "9.24") (pin "7") (pinfunction "VO_7") (pintype "bidirectional"))
      (node (ref "JP1") (pin "1") (pinfunction "1_1") (pintype "passive"))
    )
    (net (code "47") (name "Net-(9.26-AN)") (class "Default")
      (node (ref "9.26") (pin "2") (pinfunction "AN_2") (pintype "bidirectional"))
      (node (ref "U$2") (pin "72") (pinfunction "26_UART1_RXD_72") (pintype "passive"))
    )
    (net (code "48") (name "Net-(9.26-CA)") (class "Default")
      (node (ref "9.26") (pin "3") (pinfunction "CA_3") (pintype "bidirectional"))
      (node (ref "R2") (pin "2") (pinfunction "2_2") (pintype "passive"))
    )
    (net (code "49") (name "Net-(9.26-VO)") (class "Default")
      (node (ref "9.26") (pin "7") (pinfunction "VO_7") (pintype "bidirectional"))
      (node (ref "JP2") (pin "1") (pinfunction "1_1") (pintype "passive"))
    )
    (net (code "50") (name "Net-(9.27-AN)") (class "Default")
      (node (ref "9.27") (pin "2") (pinfunction "AN_2") (pintype "bidirectional"))
      (node (ref "U$2") (pin "73") (pinfunction "27_GPIO115_73") (pintype "passive"))
    )
    (net (code "51") (name "Net-(9.27-CA)") (class "Default")
      (node (ref "9.27") (pin "3") (pinfunction "CA_3") (pintype "bidirectional"))
      (node (ref "R12") (pin "2") (pinfunction "2_2") (pintype "passive"))
    )
    (net (code "52") (name "Net-(9.27-VO)") (class "Default")
      (node (ref "9.27") (pin "7") (pinfunction "VO_7") (pintype "bidirectional"))
      (node (ref "JP53") (pin "1") (pinfunction "1_1") (pintype "passive"))
    )
    (net (code "53") (name "Net-(9.41-AN)") (class "Default")
      (node (ref "9.41") (pin "2") (pinfunction "AN_2") (pintype "bidirectional"))
      (node (ref "U$2") (pin "87") (pinfunction "41_GPIO20_87") (pintype "input"))
    )
    (net (code "54") (name "Net-(9.41-CA)") (class "Default")
      (node (ref "9.41") (pin "3") (pinfunction "CA_3") (pintype "bidirectional"))
      (node (ref "R13") (pin "2") (pinfunction "2_2") (pintype "passive"))
    )
    (net (code "55") (name "Net-(9.41-VO)") (class "Default")
      (node (ref "9.41") (pin "7") (pinfunction "VO_7") (pintype "bidirectional"))
      (node (ref "JP54") (pin "1") (pinfunction "1_1") (pintype "passive"))
    )
    (net (code "56") (name "Net-(1111-AN)") (class "Default")
      (node (ref "1111") (pin "2") (pinfunction "AN_2") (pintype "bidirectional"))
      (node (ref "U$2") (pin "75") (pinfunction "29_SPI1_DO_75") (pintype "passive"))
    )
    (net (code "57") (name "Net-(1111-CA)") (class "Default")
      (node (ref "1111") (pin "3") (pinfunction "CA_3") (pintype "bidirectional"))
      (node (ref "R15") (pin "2") (pinfunction "2_2") (pintype "passive"))
    )
    (net (code "58") (name "Net-(1111-EN)") (class "Default")
      (node (ref "1111") (pin "5") (pinfunction "GND_5") (pintype "bidirectional"))
      (node (ref "1111") (pin "6") (pinfunction "EN_6") (pintype "bidirectional"))
      (node (ref "C15") (pin "2") (pinfunction "2_2") (pintype "passive"))
      (node (ref "JP48") (pin "1") (pinfunction "1_1") (pintype "passive"))
      (node (ref "R17") (pin "1") (pinfunction "1_1") (pintype "passive"))
    )
    (net (code "59") (name "Net-(1111-VCC)") (class "Default")
      (node (ref "1111") (pin "8") (pinfunction "VCC_8") (pintype "bidirectional"))
      (node (ref "C15") (pin "1") (pinfunction "1_1") (pintype "passive"))
      (node (ref "JP50") (pin "1") (pinfunction "1_1") (pintype "passive"))
    )
    (net (code "60") (name "Net-(1111-VO)") (class "Default")
      (node (ref "1111") (pin "7") (pinfunction "VO_7") (pintype "bidirectional"))
      (node (ref "JP49") (pin "1") (pinfunction "1_1") (pintype "passive"))
      (node (ref "R17") (pin "2") (pinfunction "2_2") (pintype "passive"))
    )
    (net (code "61") (name "Net-(JP7-Pad1)") (class "Default")
      (node (ref "JP7") (pin "1") (pinfunction "1_1") (pintype "passive"))
      (node (ref "R19") (pin "2") (pinfunction "2_2") (pintype "passive"))
    )
    (net (code "62") (name "Net-(JP9-Pad1)") (class "Default")
      (node (ref "JP9") (pin "1") (pinfunction "1_1") (pintype "passive"))
      (node (ref "R43") (pin "2") (pinfunction "2_2") (pintype "passive"))
    )
    (net (code "63") (name "Net-(JP20-Pad1)") (class "Default")
      (node (ref "JP20") (pin "1") (pinfunction "1_1") (pintype "passive"))
      (node (ref "R37") (pin "2") (pinfunction "2_2") (pintype "passive"))
    )
    (net (code "64") (name "Net-(JP22-Pad1)") (class "Default")
      (node (ref "JP22") (pin "1") (pinfunction "1_1") (pintype "passive"))
      (node (ref "R25") (pin "2") (pinfunction "2_2") (pintype "passive"))
    )
    (net (code "65") (name "Net-(JP24-Pad1)") (class "Default")
      (node (ref "JP24") (pin "1") (pinfunction "1_1") (pintype "passive"))
      (node (ref "R31") (pin "2") (pinfunction "2_2") (pintype "passive"))
    )
    (net (code "66") (name "Net-(JP26-Pad1)") (class "Default")
      (node (ref "JP26") (pin "1") (pinfunction "1_1") (pintype "passive"))
      (node (ref "R33") (pin "2") (pinfunction "2_2") (pintype "passive"))
    )
    (net (code "67") (name "Net-(JP28-Pad1)") (class "Default")
      (node (ref "JP28") (pin "1") (pinfunction "1_1") (pintype "passive"))
      (node (ref "R27") (pin "2") (pinfunction "2_2") (pintype "passive"))
    )
    (net (code "68") (name "Net-(JP30-Pad1)") (class "Default")
      (node (ref "JP30") (pin "1") (pinfunction "1_1") (pintype "passive"))
      (node (ref "R29") (pin "2") (pinfunction "2_2") (pintype "passive"))
    )
    (net (code "69") (name "Net-(JP32-Pad1)") (class "Default")
      (node (ref "JP32") (pin "1") (pinfunction "1_1") (pintype "passive"))
      (node (ref "R21") (pin "2") (pinfunction "2_2") (pintype "passive"))
    )
    (net (code "70") (name "Net-(JP34-Pad1)") (class "Default")
      (node (ref "JP34") (pin "1") (pinfunction "1_1") (pintype "passive"))
      (node (ref "R23") (pin "2") (pinfunction "2_2") (pintype "passive"))
    )
    (net (code "71") (name "Net-(JP36-Pad1)") (class "Default")
      (node (ref "JP36") (pin "1") (pinfunction "1_1") (pintype "passive"))
      (node (ref "R35") (pin "2") (pinfunction "2_2") (pintype "passive"))
    )
    (net (code "72") (name "Net-(LED1-C)") (class "Default")
      (node (ref "LED1") (pin "K") (pinfunction "C_K") (pintype "passive"))
      (node (ref "R42") (pin "2") (pinfunction "2_2") (pintype "passive"))
    )
    (net (code "73") (name "Net-(SPICS1-+)") (class "Default")
      (node (ref "JP12") (pin "1") (pinfunction "1_1") (pintype "passive"))
      (node (ref "SPICS1") (pin "4") (pinfunction "+_4") (pintype "bidirectional"))
    )
    (net (code "74") (name "Net-(SPICS1--)") (class "Default")
      (node (ref "JP13") (pin "1") (pinfunction "1_1") (pintype "passive"))
      (node (ref "SPICS1") (pin "3") (pinfunction "-_3") (pintype "bidirectional"))
    )
    (net (code "75") (name "Net-(SPICS1-A)") (class "Default")
      (node (ref "SPICS1") (pin "1") (pinfunction "A_1") (pintype "bidirectional"))
      (node (ref "U$2") (pin "69") (pinfunction "23_GPIO49_69") (pintype "passive"))
    )
    (net (code "76") (name "Net-(SPICS1-C)") (class "Default")
      (node (ref "R40") (pin "2") (pinfunction "2_2") (pintype "passive"))
      (node (ref "SPICS1") (pin "2") (pinfunction "C_2") (pintype "bidirectional"))
    )
    (net (code "77") (name "Net-(SPICS2-+)") (class "Default")
      (node (ref "JP16") (pin "1") (pinfunction "1_1") (pintype "passive"))
      (node (ref "SPICS2") (pin "4") (pinfunction "+_4") (pintype "bidirectional"))
    )
    (net (code "78") (name "Net-(SPICS2--)") (class "Default")
      (node (ref "JP17") (pin "1") (pinfunction "1_1") (pintype "passive"))
      (node (ref "SPICS2") (pin "3") (pinfunction "-_3") (pintype "bidirectional"))
    )
    (net (code "79") (name "Net-(SPICS2-A)") (class "Default")
      (node (ref "SPICS2") (pin "1") (pinfunction "A_1") (pintype "bidirectional"))
      (node (ref "U$2") (pin "67") (pinfunction "21_SPI0_DO_67") (pintype "passive"))
    )
    (net (code "80") (name "Net-(SPICS2-C)") (class "Default")
      (node (ref "R41") (pin "2") (pinfunction "2_2") (pintype "passive"))
      (node (ref "SPICS2") (pin "2") (pinfunction "C_2") (pintype "bidirectional"))
    )
    (net (code "81") (name "Net-(SPICS3-+)") (class "Default")
      (node (ref "JP14") (pin "1") (pinfunction "1_1") (pintype "passive"))
      (node (ref "SPICS3") (pin "4") (pinfunction "+_4") (pintype "bidirectional"))
    )
    (net (code "82") (name "Net-(SPICS3--)") (class "Default")
      (node (ref "JP15") (pin "1") (pinfunction "1_1") (pintype "passive"))
      (node (ref "SPICS3") (pin "3") (pinfunction "-_3") (pintype "bidirectional"))
    )
    (net (code "83") (name "Net-(SPICS3-A)") (class "Default")
      (node (ref "SPICS3") (pin "1") (pinfunction "A_1") (pintype "bidirectional"))
      (node (ref "U$2") (pin "63") (pinfunction "17_SPI0_CSO_63") (pintype "passive"))
    )
    (net (code "84") (name "Net-(SPICS3-C)") (class "Default")
      (node (ref "R44") (pin "2") (pinfunction "2_2") (pintype "passive"))
      (node (ref "SPICS3") (pin "2") (pinfunction "C_2") (pintype "bidirectional"))
    )
    (net (code "85") (name "Net-(SPICS4-+)") (class "Default")
      (node (ref "JP18") (pin "1") (pinfunction "1_1") (pintype "passive"))
      (node (ref "SPICS4") (pin "4") (pinfunction "+_4") (pintype "bidirectional"))
    )
    (net (code "86") (name "Net-(SPICS4--)") (class "Default")
      (node (ref "JP19") (pin "1") (pinfunction "1_1") (pintype "passive"))
      (node (ref "SPICS4") (pin "3") (pinfunction "-_3") (pintype "bidirectional"))
    )
    (net (code "87") (name "Net-(SPICS4-A)") (class "Default")
      (node (ref "SPICS4") (pin "1") (pinfunction "A_1") (pintype "bidirectional"))
      (node (ref "U$2") (pin "76") (pinfunction "30_GPIO112_76") (pintype "passive"))
    )
    (net (code "88") (name "Net-(SPICS4-C)") (class "Default")
      (node (ref "R45") (pin "2") (pinfunction "2_2") (pintype "passive"))
      (node (ref "SPICS4") (pin "2") (pinfunction "C_2") (pintype "bidirectional"))
    )
    (net (code "89") (name "Net-(TPS73133-EN)") (class "Default")
      (node (ref "C16") (pin "1") (pinfunction "1_1") (pintype "passive"))
      (node (ref "C24") (pin "1") (pinfunction "1_1") (pintype "passive"))
      (node (ref "C25") (pin "1") (pinfunction "1_1") (pintype "passive"))
      (node (ref "TPS73133") (pin "1") (pinfunction "IN_1") (pintype "bidirectional"))
      (node (ref "TPS73133") (pin "3") (pinfunction "EN_3") (pintype "bidirectional"))
      (node (ref "U$16") (pin "P$1") (pinfunction "1_P$1") (pintype "passive"))
      (node (ref "U$18") (pin "3") (pinfunction "IN_3") (pintype "bidirectional"))
      (node (ref "U$2") (pin "51") (pinfunction "5_VDD_5V_51") (pintype "power_in"))
      (node (ref "U$2") (pin "52") (pinfunction "6_VDD_5V_52") (pintype "power_in"))
    )
    (net (code "90") (name "Net-(TPS73133-NC{slash}FB)") (class "Default")
      (node (ref "C18") (pin "1") (pinfunction "1_1") (pintype "passive"))
      (node (ref "TPS73133") (pin "4") (pinfunction "NC/FB_4") (pintype "bidirectional"))
    )
    (net (code "91") (name "Net-(U$1-+)") (class "Default")
      (node (ref "R39") (pin "1") (pinfunction "1_1") (pintype "passive"))
      (node (ref "U$1") (pin "4") (pinfunction "+_4") (pintype "bidirectional"))
      (node (ref "U$2") (pin "61") (pinfunction "15_GPIO48_61") (pintype "passive"))
    )
    (net (code "92") (name "Net-(U$1-A)") (class "Default")
      (node (ref "JP8") (pin "1") (pinfunction "1_1") (pintype "passive"))
      (node (ref "U$1") (pin "1") (pinfunction "A_1") (pintype "bidirectional"))
    )
    (net (code "93") (name "Net-(U$1-C)") (class "Default")
      (node (ref "R43") (pin "1") (pinfunction "1_1") (pintype "passive"))
      (node (ref "U$1") (pin "2") (pinfunction "C_2") (pintype "bidirectional"))
    )
    (net (code "94") (name "Net-(U$2-8_GPIO67)") (class "Default")
      (node (ref "R24") (pin "1") (pinfunction "1_1") (pintype "passive"))
      (node (ref "U$2") (pin "8") (pinfunction "8_GPIO67_8") (pintype "passive"))
      (node (ref "U$9") (pin "4") (pinfunction "+_4") (pintype "bidirectional"))
    )
    (net (code "95") (name "Net-(U$2-11_GPIO45)") (class "Default")
      (node (ref "U$2") (pin "11") (pinfunction "11_GPIO45_11") (pintype "passive"))
      (node (ref "U$3") (pin "P$32") (pinfunction "32-NSHTDN_P$32") (pintype "bidirectional"))
    )
    (net (code "96") (name "Net-(U$2-11_UART4_RXD)") (class "Default")
      (node (ref "R18") (pin "1") (pinfunction "1_1") (pintype "passive"))
      (node (ref "U$2") (pin "57") (pinfunction "11_UART4_RXD_57") (pintype "passive"))
      (node (ref "U$6") (pin "4") (pinfunction "+_4") (pintype "bidirectional"))
    )
    (net (code "97") (name "Net-(U$2-17_GPIO27)") (class "Default")
      (node (ref "R22") (pin "1") (pinfunction "1_1") (pintype "passive"))
      (node (ref "U$2") (pin "17") (pinfunction "17_GPIO27_17") (pintype "passive"))
      (node (ref "U$8") (pin "4") (pinfunction "+_4") (pintype "bidirectional"))
    )
    (net (code "98") (name "Net-(U$2-18_GPIO65)") (class "Default")
      (node (ref "R20") (pin "1") (pinfunction "1_1") (pintype "passive"))
      (node (ref "U$2") (pin "18") (pinfunction "18_GPIO65_18") (pintype "passive"))
      (node (ref "U$7") (pin "4") (pinfunction "+_4") (pintype "bidirectional"))
    )
    (net (code "99") (name "Net-(U$2-25_GPIO117)") (class "Default")
      (node (ref "LED1") (pin "A") (pinfunction "A_A") (pintype "passive"))
      (node (ref "U$2") (pin "71") (pinfunction "25_GPIO117_71") (pintype "passive"))
    )
    (net (code "100") (name "Net-(U$2-27_LCD_VSYNC)") (class "Default")
      (node (ref "U$2") (pin "27") (pinfunction "27_LCD_VSYNC_27") (pintype "passive"))
      (node (ref "U$3") (pin "P$28") (pinfunction "28-D25_P$28") (pintype "bidirectional"))
    )
    (net (code "101") (name "Net-(U$2-28_LCD_PCLK)") (class "Default")
      (node (ref "U$2") (pin "28") (pinfunction "28_LCD_PCLK_28") (pintype "passive"))
      (node (ref "U$3") (pin "P$31") (pinfunction "31-CLKIN_P$31") (pintype "bidirectional"))
    )
    (net (code "102") (name "Net-(U$2-29_LCD_HSYNC)") (class "Default")
      (node (ref "U$2") (pin "29") (pinfunction "29_LCD_HSYNC_29") (pintype "passive"))
      (node (ref "U$3") (pin "P$27") (pinfunction "27-D24_P$27") (pintype "bidirectional"))
    )
    (net (code "103") (name "Net-(U$2-31_LCD_DATA14)") (class "Default")
      (node (ref "U$2") (pin "31") (pinfunction "31_LCD_DATA14_31") (pintype "passive"))
      (node (ref "U$3") (pin "P$56") (pinfunction "56-D4_P$56") (pintype "bidirectional"))
    )
    (net (code "104") (name "Net-(U$2-32_LCD_DATA15)") (class "Default")
      (node (ref "U$2") (pin "32") (pinfunction "32_LCD_DATA15_32") (pintype "passive"))
      (node (ref "U$3") (pin "P$3") (pinfunction "3-D6_P$3") (pintype "bidirectional"))
    )
    (net (code "105") (name "Net-(U$2-32_VDD_ADC)") (class "Default")
      (node (ref "JP10") (pin "1") (pinfunction "1_1") (pintype "passive"))
      (node (ref "U$2") (pin "78") (pinfunction "32_VDD_ADC_78") (pintype "passive"))
    )
    (net (code "106") (name "Net-(U$2-33_LCD_DATA13)") (class "Default")
      (node (ref "U$2") (pin "33") (pinfunction "33_LCD_DATA13_33") (pintype "passive"))
      (node (ref "U$3") (pin "P$55") (pinfunction "55-D3_P$55") (pintype "bidirectional"))
    )
    (net (code "107") (name "Net-(U$2-34_GNDA_ADC)") (class "Default")
      (node (ref "JP11") (pin "1") (pinfunction "1_1") (pintype "passive"))
      (node (ref "U$2") (pin "80") (pinfunction "34_GNDA_ADC_80") (pintype "passive"))
    )
    (net (code "108") (name "Net-(U$2-34_LCD_DATA11)") (class "Default")
      (node (ref "U$2") (pin "34") (pinfunction "34_LCD_DATA11_34") (pintype "passive"))
      (node (ref "U$3") (pin "P$52") (pinfunction "52-D1_P$52") (pintype "bidirectional"))
    )
    (net (code "109") (name "Net-(U$2-35_LCD_DATA12)") (class "Default")
      (node (ref "U$2") (pin "35") (pinfunction "35_LCD_DATA12_35") (pintype "passive"))
      (node (ref "U$3") (pin "P$54") (pinfunction "54-D2_P$54") (pintype "bidirectional"))
    )
    (net (code "110") (name "Net-(U$2-36_LCD_DATA10)") (class "Default")
      (node (ref "U$2") (pin "36") (pinfunction "36_LCD_DATA10_36") (pintype "passive"))
      (node (ref "U$3") (pin "P$14") (pinfunction "14-D14_P$14") (pintype "bidirectional"))
    )
    (net (code "111") (name "Net-(U$2-37_AIN2)") (class "Default")
      (node (ref "CN1") (pin "2") (pinfunction "2_2") (pintype "bidirectional"))
      (node (ref "U$2") (pin "83") (pinfunction "37_AIN2_83") (pintype "passive"))
    )
    (net (code "112") (name "Net-(U$2-37_LCD_DATA8)") (class "Default")
      (node (ref "U$2") (pin "37") (pinfunction "37_LCD_DATA8_37") (pintype "passive"))
      (node (ref "U$3") (pin "P$11") (pinfunction "11-D12_P$11") (pintype "bidirectional"))
    )
    (net (code "113") (name "Net-(U$2-38_AIN3)") (class "Default")
      (node (ref "CN1") (pin "1") (pinfunction "1_1") (pintype "bidirectional"))
      (node (ref "U$2") (pin "84") (pinfunction "38_AIN3_84") (pintype "passive"))
    )
    (net (code "114") (name "Net-(U$2-38_LCD_DATA9)") (class "Default")
      (node (ref "U$2") (pin "38") (pinfunction "38_LCD_DATA9_38") (pintype "passive"))
      (node (ref "U$3") (pin "P$12") (pinfunction "12-D13_P$12") (pintype "bidirectional"))
    )
    (net (code "115") (name "Net-(U$2-39_AIN0)") (class "Default")
      (node (ref "CN1") (pin "4") (pinfunction "4_4") (pintype "bidirectional"))
      (node (ref "U$2") (pin "85") (pinfunction "39_AIN0_85") (pintype "power_in"))
    )
    (net (code "116") (name "Net-(U$2-39_LCD_DATA6)") (class "Default")
      (node (ref "U$2") (pin "39") (pinfunction "39_LCD_DATA6_39") (pintype "passive"))
      (node (ref "U$3") (pin "P$6") (pinfunction "6-D8_P$6") (pintype "bidirectional"))
    )
    (net (code "117") (name "Net-(U$2-40_AIN1)") (class "Default")
      (node (ref "CN1") (pin "3") (pinfunction "3_3") (pintype "bidirectional"))
      (node (ref "U$2") (pin "86") (pinfunction "40_AIN1_86") (pintype "passive"))
    )
    (net (code "118") (name "Net-(U$2-40_LCD_DATA7)") (class "Default")
      (node (ref "U$2") (pin "40") (pinfunction "40_LCD_DATA7_40") (pintype "passive"))
      (node (ref "U$3") (pin "P$7") (pinfunction "7-D9_P$7") (pintype "bidirectional"))
    )
    (net (code "119") (name "Net-(U$2-41_LCD_DATA4)") (class "Default")
      (node (ref "U$2") (pin "41") (pinfunction "41_LCD_DATA4_41") (pintype "passive"))
      (node (ref "U$3") (pin "P$24") (pinfunction "24-D22_P$24") (pintype "bidirectional"))
    )
    (net (code "120") (name "Net-(U$2-42_LCD_DATA5)") (class "Default")
      (node (ref "U$2") (pin "42") (pinfunction "42_LCD_DATA5_42") (pintype "passive"))
      (node (ref "U$3") (pin "P$4") (pinfunction "4-D7_P$4") (pintype "bidirectional"))
    )
    (net (code "121") (name "Net-(U$2-43_LCD_DATA2)") (class "Default")
      (node (ref "U$2") (pin "43") (pinfunction "43_LCD_DATA2_43") (pintype "passive"))
      (node (ref "U$3") (pin "P$22") (pinfunction "22-D20_P$22") (pintype "bidirectional"))
    )
    (net (code "122") (name "Net-(U$2-44_LCD_DATA3)") (class "Default")
      (node (ref "U$2") (pin "44") (pinfunction "44_LCD_DATA3_44") (pintype "passive"))
      (node (ref "U$3") (pin "P$23") (pinfunction "23-D21_P$23") (pintype "bidirectional"))
    )
    (net (code "123") (name "Net-(U$2-45_LCD_DATA0)") (class "Default")
      (node (ref "U$2") (pin "45") (pinfunction "45_LCD_DATA0_45") (pintype "passive"))
      (node (ref "U$3") (pin "P$19") (pinfunction "19-D18_P$19") (pintype "bidirectional"))
    )
    (net (code "124") (name "Net-(U$2-46_LCD_DATA1)") (class "Default")
      (node (ref "U$2") (pin "46") (pinfunction "46_LCD_DATA1_46") (pintype "passive"))
      (node (ref "U$3") (pin "P$20") (pinfunction "20-D19_P$20") (pintype "bidirectional"))
    )
    (net (code "125") (name "Net-(U$3-15-D15)") (class "Default")
      (node (ref "U$3") (pin "P$15") (pinfunction "15-D15_P$15") (pintype "bidirectional"))
      (node (ref "U$33") (pin "P$1") (pinfunction "1_P$1") (pintype "passive"))
    )
    (net (code "126") (name "Net-(U$3-37-Y3P)") (class "Default")
      (node (ref "U$3") (pin "P$37") (pinfunction "37-Y3P_P$37") (pintype "bidirectional"))
      (node (ref "U$4") (pin "10") (pinfunction "10_10") (pintype "passive"))
    )
    (net (code "127") (name "Net-(U$3-38-Y3M)") (class "Default")
      (node (ref "U$3") (pin "P$38") (pinfunction "38-Y3M_P$38") (pintype "bidirectional"))
      (node (ref "U$4") (pin "9") (pinfunction "9_9") (pintype "passive"))
    )
    (net (code "128") (name "Net-(U$3-39-CLKOUTP)") (class "Default")
      (node (ref "U$3") (pin "P$39") (pinfunction "39-CLKOUTP_P$39") (pintype "bidirectional"))
      (node (ref "U$4") (pin "8") (pinfunction "8_8") (pintype "passive"))
    )
    (net (code "129") (name "Net-(U$3-40-CLKOUTM)") (class "Default")
      (node (ref "U$3") (pin "P$40") (pinfunction "40-CLKOUTM_P$40") (pintype "bidirectional"))
      (node (ref "U$4") (pin "7") (pinfunction "7_7") (pintype "passive"))
    )
    (net (code "130") (name "Net-(U$3-41-Y2P)") (class "Default")
      (node (ref "U$3") (pin "P$41") (pinfunction "41-Y2P_P$41") (pintype "bidirectional"))
      (node (ref "U$4") (pin "6") (pinfunction "6_6") (pintype "passive"))
    )
    (net (code "131") (name "Net-(U$3-42-Y2M)") (class "Default")
      (node (ref "U$3") (pin "P$42") (pinfunction "42-Y2M_P$42") (pintype "bidirectional"))
      (node (ref "U$4") (pin "5") (pinfunction "5_5") (pintype "passive"))
    )
    (net (code "132") (name "Net-(U$3-45-Y1P)") (class "Default")
      (node (ref "U$3") (pin "P$45") (pinfunction "45-Y1P_P$45") (pintype "bidirectional"))
      (node (ref "U$4") (pin "4") (pinfunction "4_4") (pintype "passive"))
    )
    (net (code "133") (name "Net-(U$3-46-Y1M)") (class "Default")
      (node (ref "U$3") (pin "P$46") (pinfunction "46-Y1M_P$46") (pintype "bidirectional"))
      (node (ref "U$4") (pin "3") (pinfunction "3_3") (pintype "passive"))
    )
    (net (code "134") (name "Net-(U$3-47-Y0P)") (class "Default")
      (node (ref "U$3") (pin "P$47") (pinfunction "47-Y0P_P$47") (pintype "bidirectional"))
      (node (ref "U$4") (pin "2") (pinfunction "2_2") (pintype "passive"))
    )
    (net (code "135") (name "Net-(U$3-48-Y0M)") (class "Default")
      (node (ref "U$3") (pin "P$48") (pinfunction "48-Y0M_P$48") (pintype "bidirectional"))
      (node (ref "U$4") (pin "1") (pinfunction "1_1") (pintype "passive"))
    )
    (net (code "136") (name "Net-(U$3-51-D0)") (class "Default")
      (node (ref "U$3") (pin "P$51") (pinfunction "51-D0_P$51") (pintype "bidirectional"))
      (node (ref "U$32") (pin "P$1") (pinfunction "1_P$1") (pintype "passive"))
    )
    (net (code "137") (name "Net-(U$5-1)") (class "Default")
      (node (ref "C23") (pin "1") (pinfunction "1_1") (pintype "passive"))
      (node (ref "U$18") (pin "2") (pinfunction "OUT_2") (pintype "bidirectional"))
      (node (ref "U$18") (pin "TAB") (pinfunction "OUT_TAB") (pintype "bidirectional"))
      (node (ref "U$4") (pin "11") (pinfunction "11_11") (pintype "passive"))
      (node (ref "U$4") (pin "12") (pinfunction "12_12") (pintype "passive"))
      (node (ref "U$5") (pin "P$1") (pinfunction "1_P$1") (pintype "passive"))
    )
    (net (code "138") (name "Net-(U$6-A)") (class "Default")
      (node (ref "JP5") (pin "1") (pinfunction "1_1") (pintype "passive"))
      (node (ref "U$6") (pin "1") (pinfunction "A_1") (pintype "bidirectional"))
    )
    (net (code "139") (name "Net-(U$6-C)") (class "Default")
      (node (ref "R19") (pin "1") (pinfunction "1_1") (pintype "passive"))
      (node (ref "U$6") (pin "2") (pinfunction "C_2") (pintype "bidirectional"))
    )
    (net (code "140") (name "Net-(U$7-A)") (class "Default")
      (node (ref "JP33") (pin "1") (pinfunction "1_1") (pintype "passive"))
      (node (ref "U$7") (pin "1") (pinfunction "A_1") (pintype "bidirectional"))
    )
    (net (code "141") (name "Net-(U$7-C)") (class "Default")
      (node (ref "R21") (pin "1") (pinfunction "1_1") (pintype "passive"))
      (node (ref "U$7") (pin "2") (pinfunction "C_2") (pintype "bidirectional"))
    )
    (net (code "142") (name "Net-(U$8-A)") (class "Default")
      (node (ref "JP35") (pin "1") (pinfunction "1_1") (pintype "passive"))
      (node (ref "U$8") (pin "1") (pinfunction "A_1") (pintype "bidirectional"))
    )
    (net (code "143") (name "Net-(U$8-C)") (class "Default")
      (node (ref "R23") (pin "1") (pinfunction "1_1") (pintype "passive"))
      (node (ref "U$8") (pin "2") (pinfunction "C_2") (pintype "bidirectional"))
    )
    (net (code "144") (name "Net-(U$9-A)") (class "Default")
      (node (ref "JP23") (pin "1") (pinfunction "1_1") (pintype "passive"))
      (node (ref "U$9") (pin "1") (pinfunction "A_1") (pintype "bidirectional"))
    )
    (net (code "145") (name "Net-(U$9-C)") (class "Default")
      (node (ref "R25") (pin "1") (pinfunction "1_1") (pintype "passive"))
      (node (ref "U$9") (pin "2") (pinfunction "C_2") (pintype "bidirectional"))
    )
    (net (code "146") (name "Net-(U$10-+)") (class "Default")
      (node (ref "R26") (pin "1") (pinfunction "1_1") (pintype "passive"))
      (node (ref "U$10") (pin "4") (pinfunction "+_4") (pintype "bidirectional"))
      (node (ref "U$2") (pin "10") (pinfunction "10_GPIO68_10") (pintype "passive"))
    )
    (net (code "147") (name "Net-(U$10-A)") (class "Default")
      (node (ref "JP29") (pin "1") (pinfunction "1_1") (pintype "passive"))
      (node (ref "U$10") (pin "1") (pinfunction "A_1") (pintype "bidirectional"))
    )
    (net (code "148") (name "Net-(U$10-C)") (class "Default")
      (node (ref "R27") (pin "1") (pinfunction "1_1") (pintype "passive"))
      (node (ref "U$10") (pin "2") (pinfunction "C_2") (pintype "bidirectional"))
    )
    (net (code "149") (name "Net-(U$11-+)") (class "Default")
      (node (ref "R28") (pin "1") (pinfunction "1_1") (pintype "passive"))
      (node (ref "U$11") (pin "4") (pinfunction "+_4") (pintype "bidirectional"))
      (node (ref "U$2") (pin "65") (pinfunction "19_I2C2_SCL_65") (pintype "passive"))
    )
    (net (code "150") (name "Net-(U$11-A)") (class "Default")
      (node (ref "JP31") (pin "1") (pinfunction "1_1") (pintype "passive"))
      (node (ref "U$11") (pin "1") (pinfunction "A_1") (pintype "bidirectional"))
    )
    (net (code "151") (name "Net-(U$11-C)") (class "Default")
      (node (ref "R29") (pin "1") (pinfunction "1_1") (pintype "passive"))
      (node (ref "U$11") (pin "2") (pinfunction "C_2") (pintype "bidirectional"))
    )
    (net (code "152") (name "Net-(U$12-+)") (class "Default")
      (node (ref "R30") (pin "1") (pinfunction "1_1") (pintype "passive"))
      (node (ref "U$12") (pin "4") (pinfunction "+_4") (pintype "bidirectional"))
      (node (ref "U$2") (pin "7") (pinfunction "7_GPIO66_7") (pintype "passive"))
    )
    (net (code "153") (name "Net-(U$12-A)") (class "Default")
      (node (ref "JP25") (pin "1") (pinfunction "1_1") (pintype "passive"))
      (node (ref "U$12") (pin "1") (pinfunction "A_1") (pintype "bidirectional"))
    )
    (net (code "154") (name "Net-(U$12-C)") (class "Default")
      (node (ref "R31") (pin "1") (pinfunction "1_1") (pintype "passive"))
      (node (ref "U$12") (pin "2") (pinfunction "C_2") (pintype "bidirectional"))
    )
    (net (code "155") (name "Net-(U$13-+)") (class "Default")
      (node (ref "R32") (pin "1") (pinfunction "1_1") (pintype "passive"))
      (node (ref "U$13") (pin "4") (pinfunction "+_4") (pintype "bidirectional"))
      (node (ref "U$2") (pin "9") (pinfunction "9_GPIO69_9") (pintype "passive"))
    )
    (net (code "156") (name "Net-(U$13-A)") (class "Default")
      (node (ref "JP27") (pin "1") (pinfunction "1_1") (pintype "passive"))
      (node (ref "U$13") (pin "1") (pinfunction "A_1") (pintype "bidirectional"))
    )
    (net (code "157") (name "Net-(U$13-C)") (class "Default")
      (node (ref "R33") (pin "1") (pinfunction "1_1") (pintype "passive"))
      (node (ref "U$13") (pin "2") (pinfunction "C_2") (pintype "bidirectional"))
    )
    (net (code "158") (name "Net-(U$14-+)") (class "Default")
      (node (ref "R34") (pin "1") (pinfunction "1_1") (pintype "passive"))
      (node (ref "U$14") (pin "4") (pinfunction "+_4") (pintype "bidirectional"))
      (node (ref "U$2") (pin "16") (pinfunction "16_GPIO46_16") (pintype "passive"))
    )
    (net (code "159") (name "Net-(U$14-A)") (class "Default")
      (node (ref "JP37") (pin "1") (pinfunction "1_1") (pintype "passive"))
      (node (ref "U$14") (pin "1") (pinfunction "A_1") (pintype "bidirectional"))
    )
    (net (code "160") (name "Net-(U$14-C)") (class "Default")
      (node (ref "R35") (pin "1") (pinfunction "1_1") (pintype "passive"))
      (node (ref "U$14") (pin "2") (pinfunction "C_2") (pintype "bidirectional"))
    )
    (net (code "161") (name "Net-(U$15-+)") (class "Default")
      (node (ref "R36") (pin "1") (pinfunction "1_1") (pintype "passive"))
      (node (ref "U$15") (pin "4") (pinfunction "+_4") (pintype "bidirectional"))
      (node (ref "U$2") (pin "58") (pinfunction "12_GPIO60_58") (pintype "passive"))
    )
    (net (code "162") (name "Net-(U$15-A)") (class "Default")
      (node (ref "JP21") (pin "1") (pinfunction "1_1") (pintype "passive"))
      (node (ref "U$15") (pin "1") (pinfunction "A_1") (pintype "bidirectional"))
    )
    (net (code "163") (name "Net-(U$15-C)") (class "Default")
      (node (ref "R37") (pin "1") (pinfunction "1_1") (pintype "passive"))
      (node (ref "U$15") (pin "2") (pinfunction "C_2") (pintype "bidirectional"))
    )
    (net (code "164") (name "Net-(U$19-1)") (class "Default")
      (node (ref "U$19") (pin "P$1") (pinfunction "1_P$1") (pintype "passive"))
      (node (ref "U$3") (pin "P$2") (pinfunction "2-D5_P$2") (pintype "bidirectional"))
    )
    (net (code "165") (name "Net-(U$20-1)") (class "Default")
      (node (ref "U$20") (pin "P$1") (pinfunction "1_P$1") (pintype "passive"))
      (node (ref "U$3") (pin "P$50") (pinfunction "50-D27_P$50") (pintype "bidirectional"))
    )
    (net (code "166") (name "Net-(U$21-1)") (class "Default")
      (node (ref "U$21") (pin "P$1") (pinfunction "1_P$1") (pintype "passive"))
      (node (ref "U$3") (pin "P$8") (pinfunction "8-D10_P$8") (pintype "bidirectional"))
    )
    (net (code "167") (name "Net-(U$22-1)") (class "Default")
      (node (ref "U$22") (pin "P$1") (pinfunction "1_P$1") (pintype "passive"))
      (node (ref "U$3") (pin "P$10") (pinfunction "10-D11_P$10") (pintype "bidirectional"))
    )
    (net (code "168") (name "Net-(U$23-1)") (class "Default")
      (node (ref "U$23") (pin "P$1") (pinfunction "1_P$1") (pintype "passive"))
      (node (ref "U$3") (pin "P$16") (pinfunction "16-D16_P$16") (pintype "bidirectional"))
    )
    (net (code "169") (name "Net-(U$24-1)") (class "Default")
      (node (ref "U$24") (pin "P$1") (pinfunction "1_P$1") (pintype "passive"))
      (node (ref "U$3") (pin "P$18") (pinfunction "18-D17_P$18") (pintype "bidirectional"))
    )
    (net (code "170") (name "Net-(U$25-1)") (class "Default")
      (node (ref "U$25") (pin "P$1") (pinfunction "1_P$1") (pintype "passive"))
      (node (ref "U$3") (pin "P$25") (pinfunction "25-D23_P$25") (pintype "bidirectional"))
    )
    (net (code "171") (name "V-") (class "Default")
      (node (ref "8.12") (pin "5") (pinfunction "GND_5") (pintype "bidirectional"))
      (node (ref "8.12") (pin "6") (pinfunction "EN_6") (pintype "bidirectional"))
      (node (ref "8.13") (pin "5") (pinfunction "GND_5") (pintype "bidirectional"))
      (node (ref "8.13") (pin "6") (pinfunction "EN_6") (pintype "bidirectional"))
      (node (ref "8.14") (pin "5") (pinfunction "GND_5") (pintype "bidirectional"))
      (node (ref "8.14") (pin "6") (pinfunction "EN_6") (pintype "bidirectional"))
      (node (ref "8.15") (pin "5") (pinfunction "GND_5") (pintype "bidirectional"))
      (node (ref "8.15") (pin "6") (pinfunction "EN_6") (pintype "bidirectional"))
      (node (ref "8.19") (pin "5") (pinfunction "GND_5") (pintype "bidirectional"))
      (node (ref "8.19") (pin "6") (pinfunction "EN_6") (pintype "bidirectional"))
      (node (ref "8.26") (pin "5") (pinfunction "GND_5") (pintype "bidirectional"))
      (node (ref "8.26") (pin "6") (pinfunction "EN_6") (pintype "bidirectional"))
      (node (ref "C10") (pin "2") (pinfunction "2_2") (pintype "passive"))
      (node (ref "C11") (pin "2") (pinfunction "2_2") (pintype "passive"))
      (node (ref "C12") (pin "2") (pinfunction "2_2") (pintype "passive"))
      (node (ref "C13") (pin "2") (pinfunction "2_2") (pintype "passive"))
      (node (ref "C8") (pin "2") (pinfunction "2_2") (pintype "passive"))
      (node (ref "C9") (pin "2") (pinfunction "2_2") (pintype "passive"))
      (node (ref "JP45") (pin "1") (pinfunction "1_1") (pintype "passive"))
    )
    (net (code "172") (name "VCC{slash}2") (class "Default")
      (node (ref "C17") (pin "1") (pinfunction "1_1") (pintype "passive"))
      (node (ref "C20") (pin "1") (pinfunction "1_1") (pintype "passive"))
      (node (ref "C21") (pin "1") (pinfunction "1_1") (pintype "passive"))
      (node (ref "C22") (pin "1") (pinfunction "1_1") (pintype "passive"))
      (node (ref "TPS73133") (pin "5") (pinfunction "OUT_5") (pintype "bidirectional"))
      (node (ref "U$3") (pin "P$1") (pinfunction "1-IOVCC_P$1") (pintype "bidirectional"))
      (node (ref "U$3") (pin "P$17") (pinfunction "17-CLKSEL_P$17") (pintype "bidirectional"))
      (node (ref "U$3") (pin "P$26") (pinfunction "26-IOVCC_P$26") (pintype "bidirectional"))
      (node (ref "U$3") (pin "P$30") (pinfunction "30-D26_P$30") (pintype "bidirectional"))
      (node (ref "U$3") (pin "P$34") (pinfunction "34-PLLVCC_P$34") (pintype "bidirectional"))
      (node (ref "U$3") (pin "P$44") (pinfunction "44-LVDSVCC_P$44") (pintype "bidirectional"))
      (node (ref "U$3") (pin "P$9") (pinfunction "9-VCC_P$9") (pintype "bidirectional"))
    )
    (net (code "173") (name "unconnected-(U$2-3_MMC1_DAT6-Pad3)") (class "Default")
      (node (ref "U$2") (pin "3") (pinfunction "3_MMC1_DAT6_3") (pintype "passive"))
    )
    (net (code "174") (name "unconnected-(U$2-4_MMC1_DAT7-Pad4)") (class "Default")
      (node (ref "U$2") (pin "4") (pinfunction "4_MMC1_DAT7_4") (pintype "passive"))
    )
    (net (code "175") (name "unconnected-(U$2-5_MMC1_DAT2-Pad5)") (class "Default")
      (node (ref "U$2") (pin "5") (pinfunction "5_MMC1_DAT2_5") (pintype "passive"))
    )
    (net (code "176") (name "unconnected-(U$2-6_MMC1_DAT3-Pad6)") (class "Default")
      (node (ref "U$2") (pin "6") (pinfunction "6_MMC1_DAT3_6") (pintype "passive"))
    )
    (net (code "177") (name "unconnected-(U$2-8_SYS_5V-Pad54)") (class "Default")
      (node (ref "U$2") (pin "54") (pinfunction "8_SYS_5V_54") (pintype "passive"))
    )
    (net (code "178") (name "unconnected-(U$2-9_PWR_BUT-Pad55)") (class "Default")
      (node (ref "U$2") (pin "55") (pinfunction "9_PWR_BUT_55") (pintype "passive"))
    )
    (net (code "179") (name "unconnected-(U$2-10_SYS_RESETN-Pad56)") (class "Default")
      (node (ref "U$2") (pin "56") (pinfunction "10_SYS_RESETN_56") (pintype "passive"))
    )
    (net (code "180") (name "unconnected-(U$2-20_I2C2_SDA-Pad66)") (class "Default")
      (node (ref "U$2") (pin "66") (pinfunction "20_I2C2_SDA_66") (pintype "passive"))
    )
    (net (code "181") (name "unconnected-(U$2-20_MMC1_CMD-Pad20)") (class "Default")
      (node (ref "U$2") (pin "20") (pinfunction "20_MMC1_CMD_20") (pintype "passive"))
    )
    (net (code "182") (name "unconnected-(U$2-21_MMC1_CLK-Pad21)") (class "Default")
      (node (ref "U$2") (pin "21") (pinfunction "21_MMC1_CLK_21") (pintype "passive"))
    )
    (net (code "183") (name "unconnected-(U$2-22_MMC1_DAT5-Pad22)") (class "Default")
      (node (ref "U$2") (pin "22") (pinfunction "22_MMC1_DAT5_22") (pintype "passive"))
    )
    (net (code "184") (name "unconnected-(U$2-22_SPI0_SCLK-Pad68)") (class "Default")
      (node (ref "U$2") (pin "68") (pinfunction "22_SPI0_SCLK_68") (pintype "passive"))
    )
    (net (code "185") (name "unconnected-(U$2-23_MMC1_DAT4-Pad23)") (class "Default")
      (node (ref "U$2") (pin "23") (pinfunction "23_MMC1_DAT4_23") (pintype "passive"))
    )
    (net (code "186") (name "unconnected-(U$2-24_MMC1_DAT1-Pad24)") (class "Default")
      (node (ref "U$2") (pin "24") (pinfunction "24_MMC1_DAT1_24") (pintype "passive"))
    )
    (net (code "187") (name "unconnected-(U$2-25_MMC1_DAT0-Pad25)") (class "Default")
      (node (ref "U$2") (pin "25") (pinfunction "25_MMC1_DAT0_25") (pintype "passive"))
    )
    (net (code "188") (name "unconnected-(U$2-28_SPI1_CSO-Pad74)") (class "Default")
      (node (ref "U$2") (pin "74") (pinfunction "28_SPI1_CSO_74") (pintype "passive"))
    )
    (net (code "189") (name "unconnected-(U$2-30_LCD_AC_BIAS-Pad30)") (class "Default")
      (node (ref "U$2") (pin "30") (pinfunction "30_LCD_AC_BIAS_30") (pintype "passive"))
    )
    (net (code "190") (name "unconnected-(U$2-31_SPI1_SCLK-Pad77)") (class "Default")
      (node (ref "U$2") (pin "77") (pinfunction "31_SPI1_SCLK_77") (pintype "passive"))
    )
    (net (code "191") (name "unconnected-(U$2-33_AIN4-Pad79)") (class "Default")
      (node (ref "U$2") (pin "79") (pinfunction "33_AIN4_79") (pintype "passive"))
    )
    (net (code "192") (name "unconnected-(U$2-35_AIN6-Pad81)") (class "Default")
      (node (ref "U$2") (pin "81") (pinfunction "35_AIN6_81") (pintype "passive"))
    )
    (net (code "193") (name "unconnected-(U$2-36_AIN5-Pad82)") (class "Default")
      (node (ref "U$2") (pin "82") (pinfunction "36_AIN5_82") (pintype "passive"))
    )
  )
)
